# omicron2.net
KiCad netlist of a schematic drawn in EAGLE
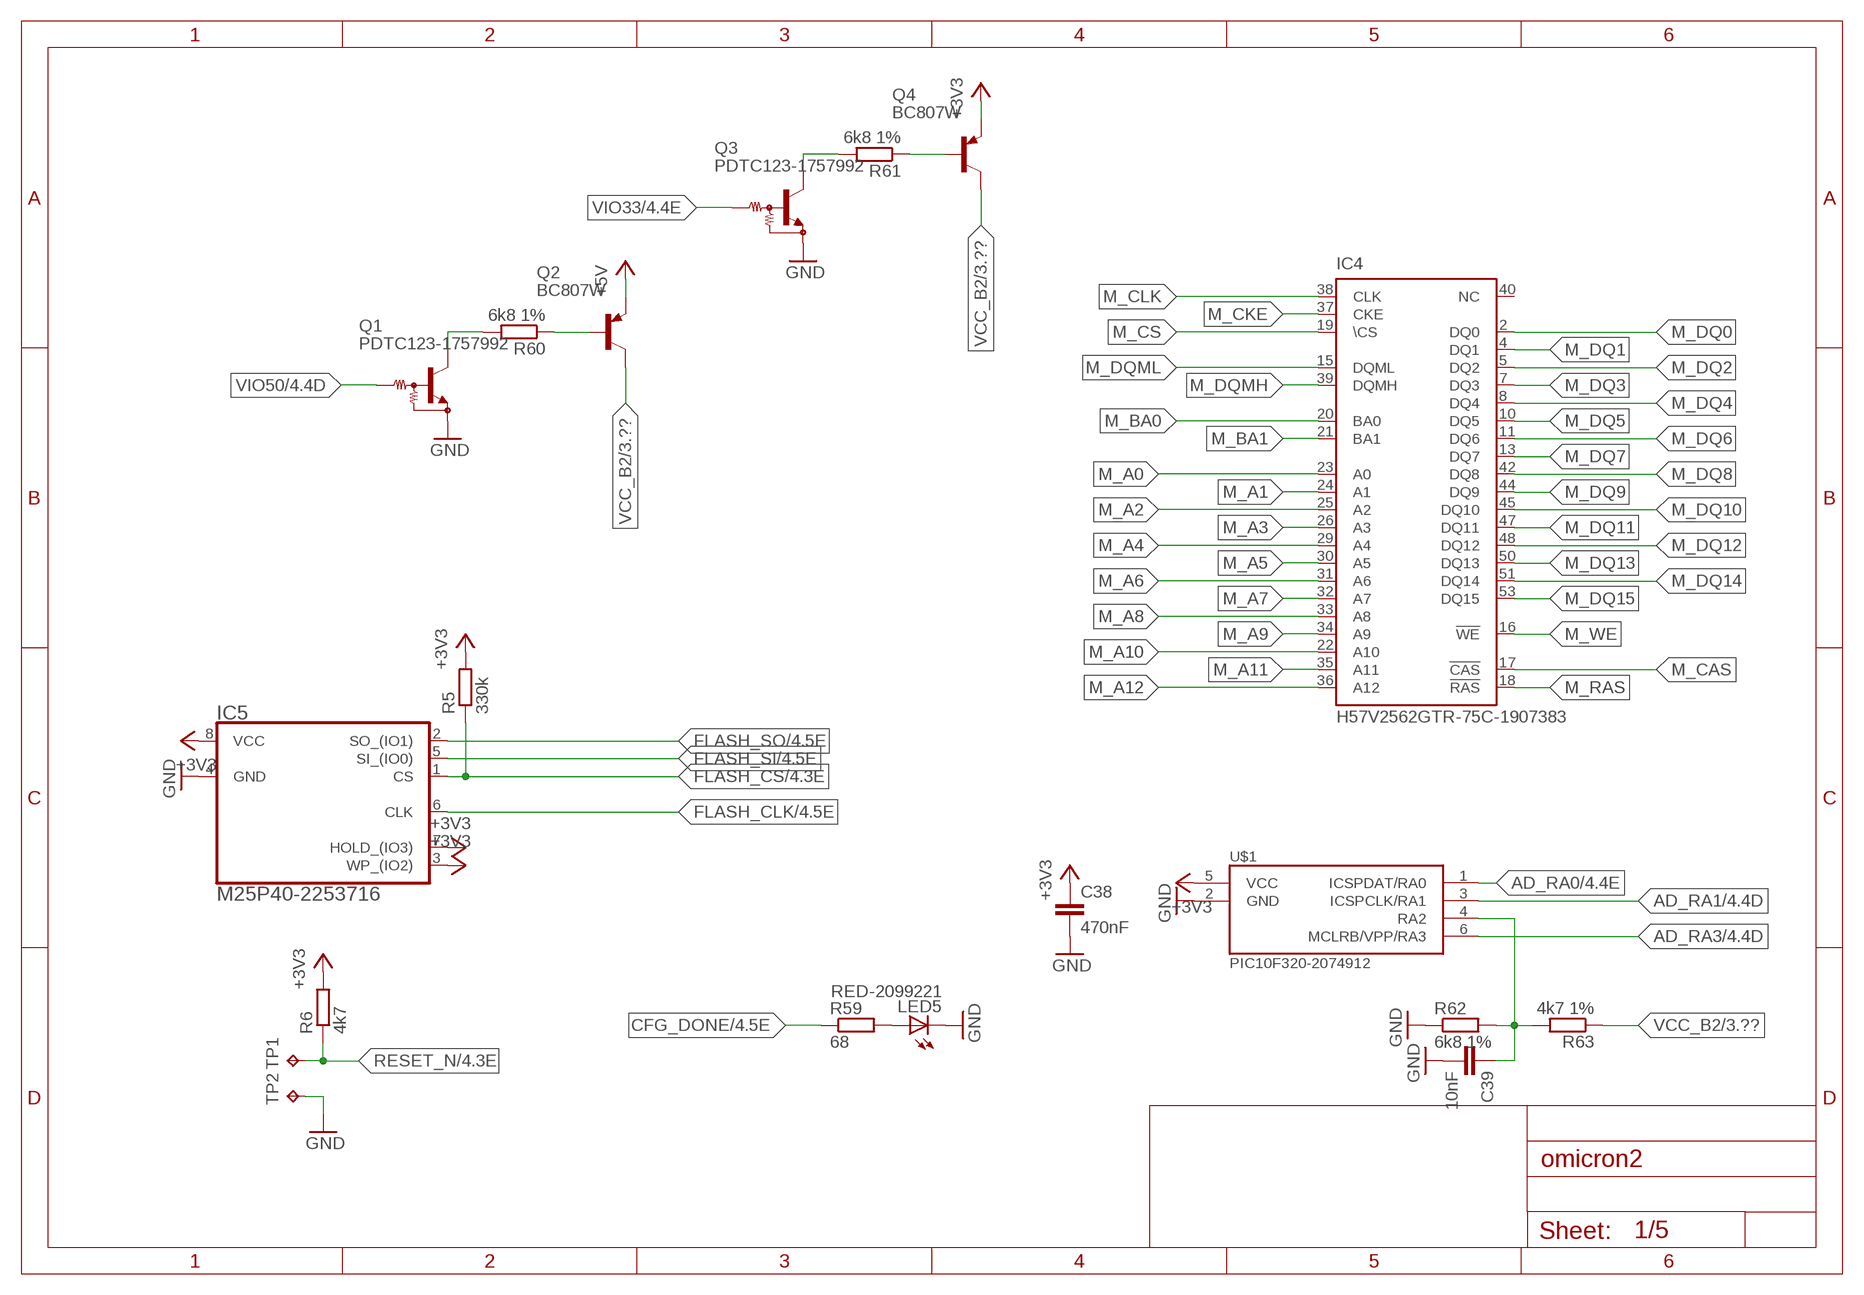
[diagram p0: schematic, sheet 1]
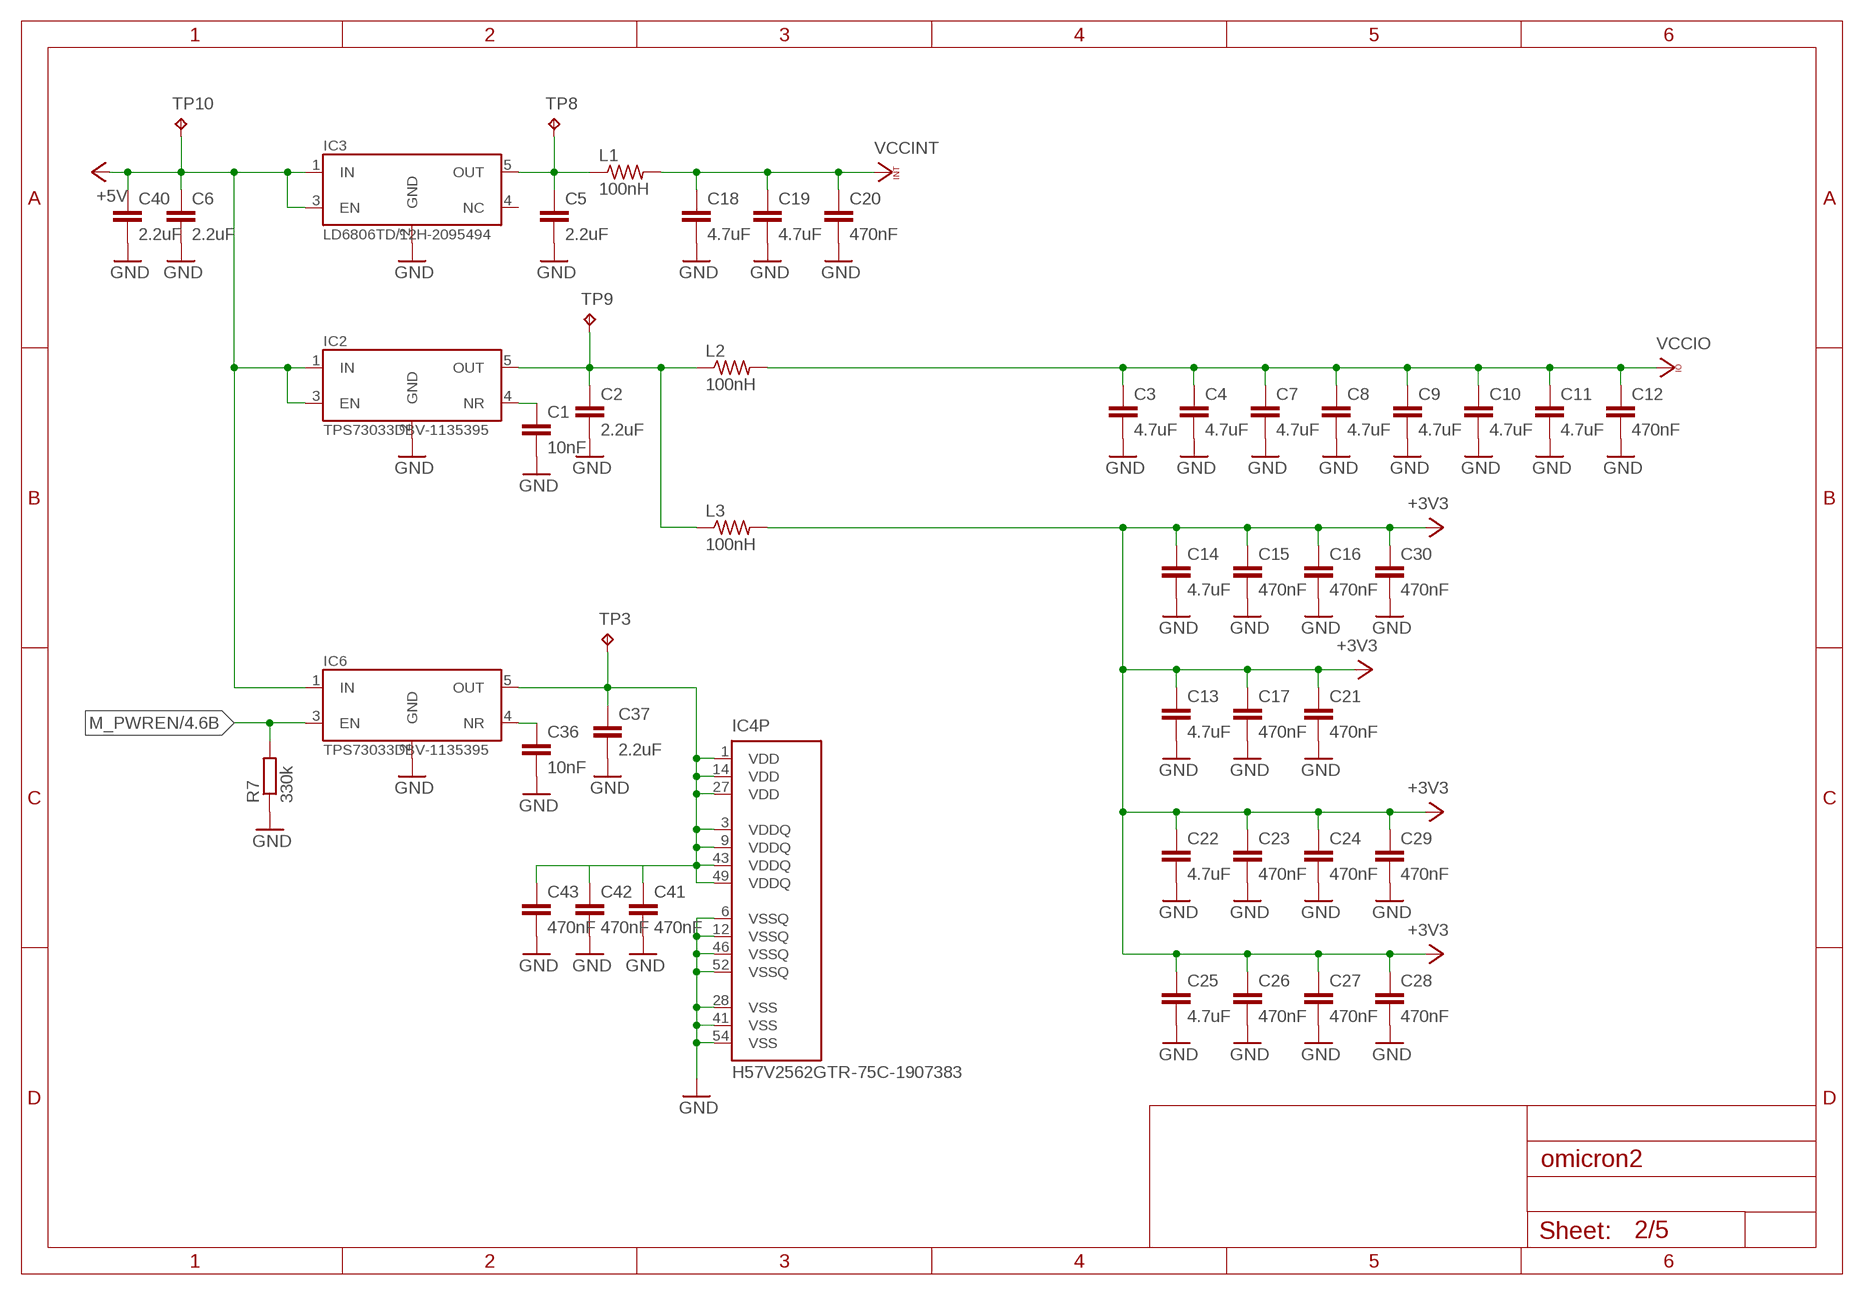
[diagram p1: schematic, sheet 2]
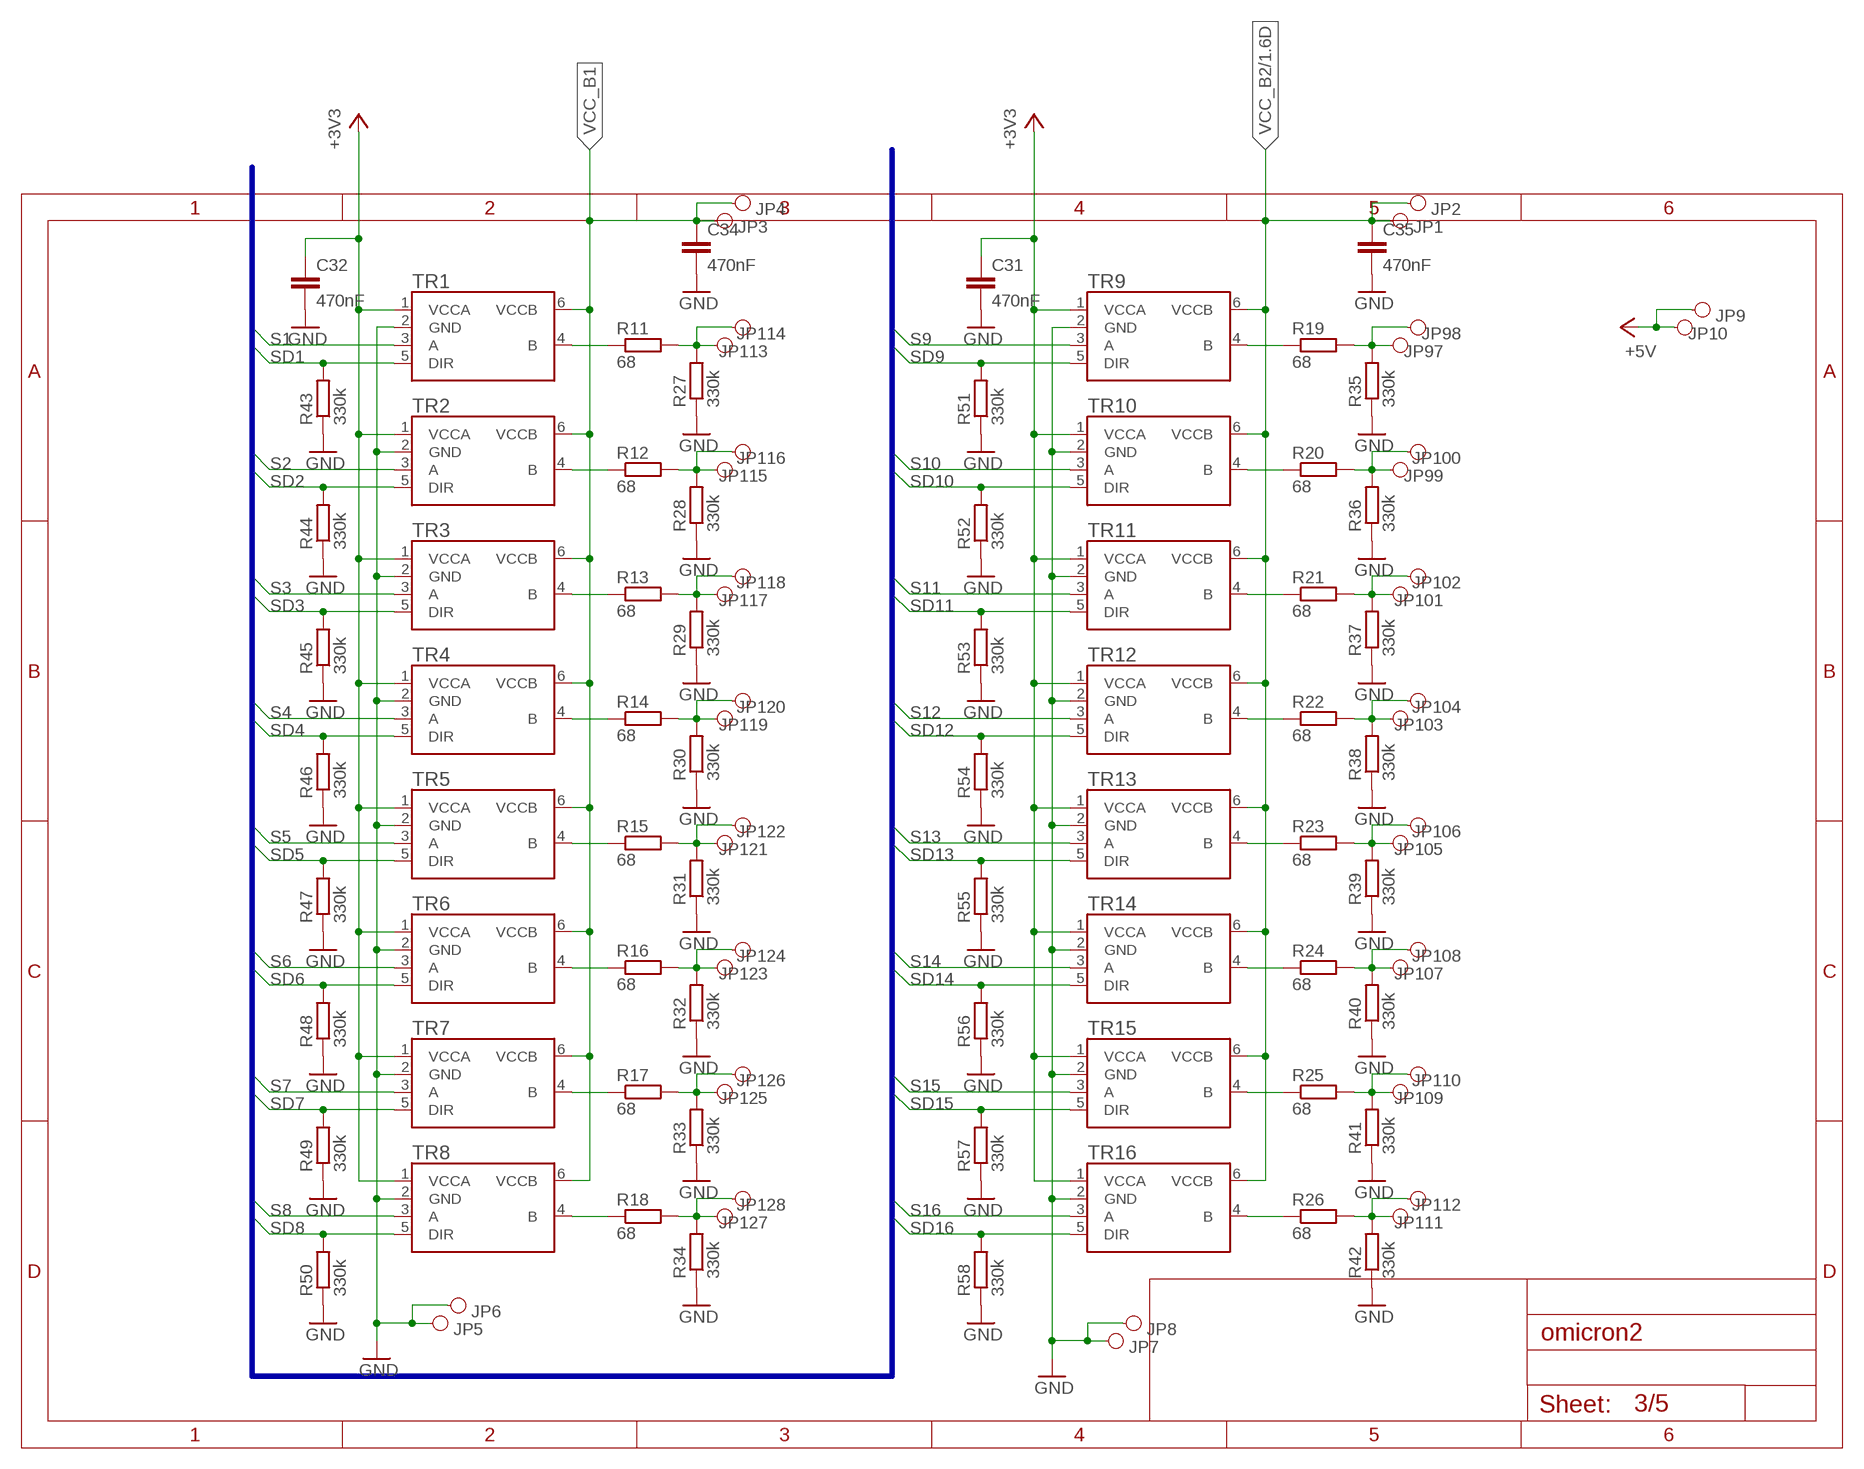
[diagram p2: schematic, sheet 3]
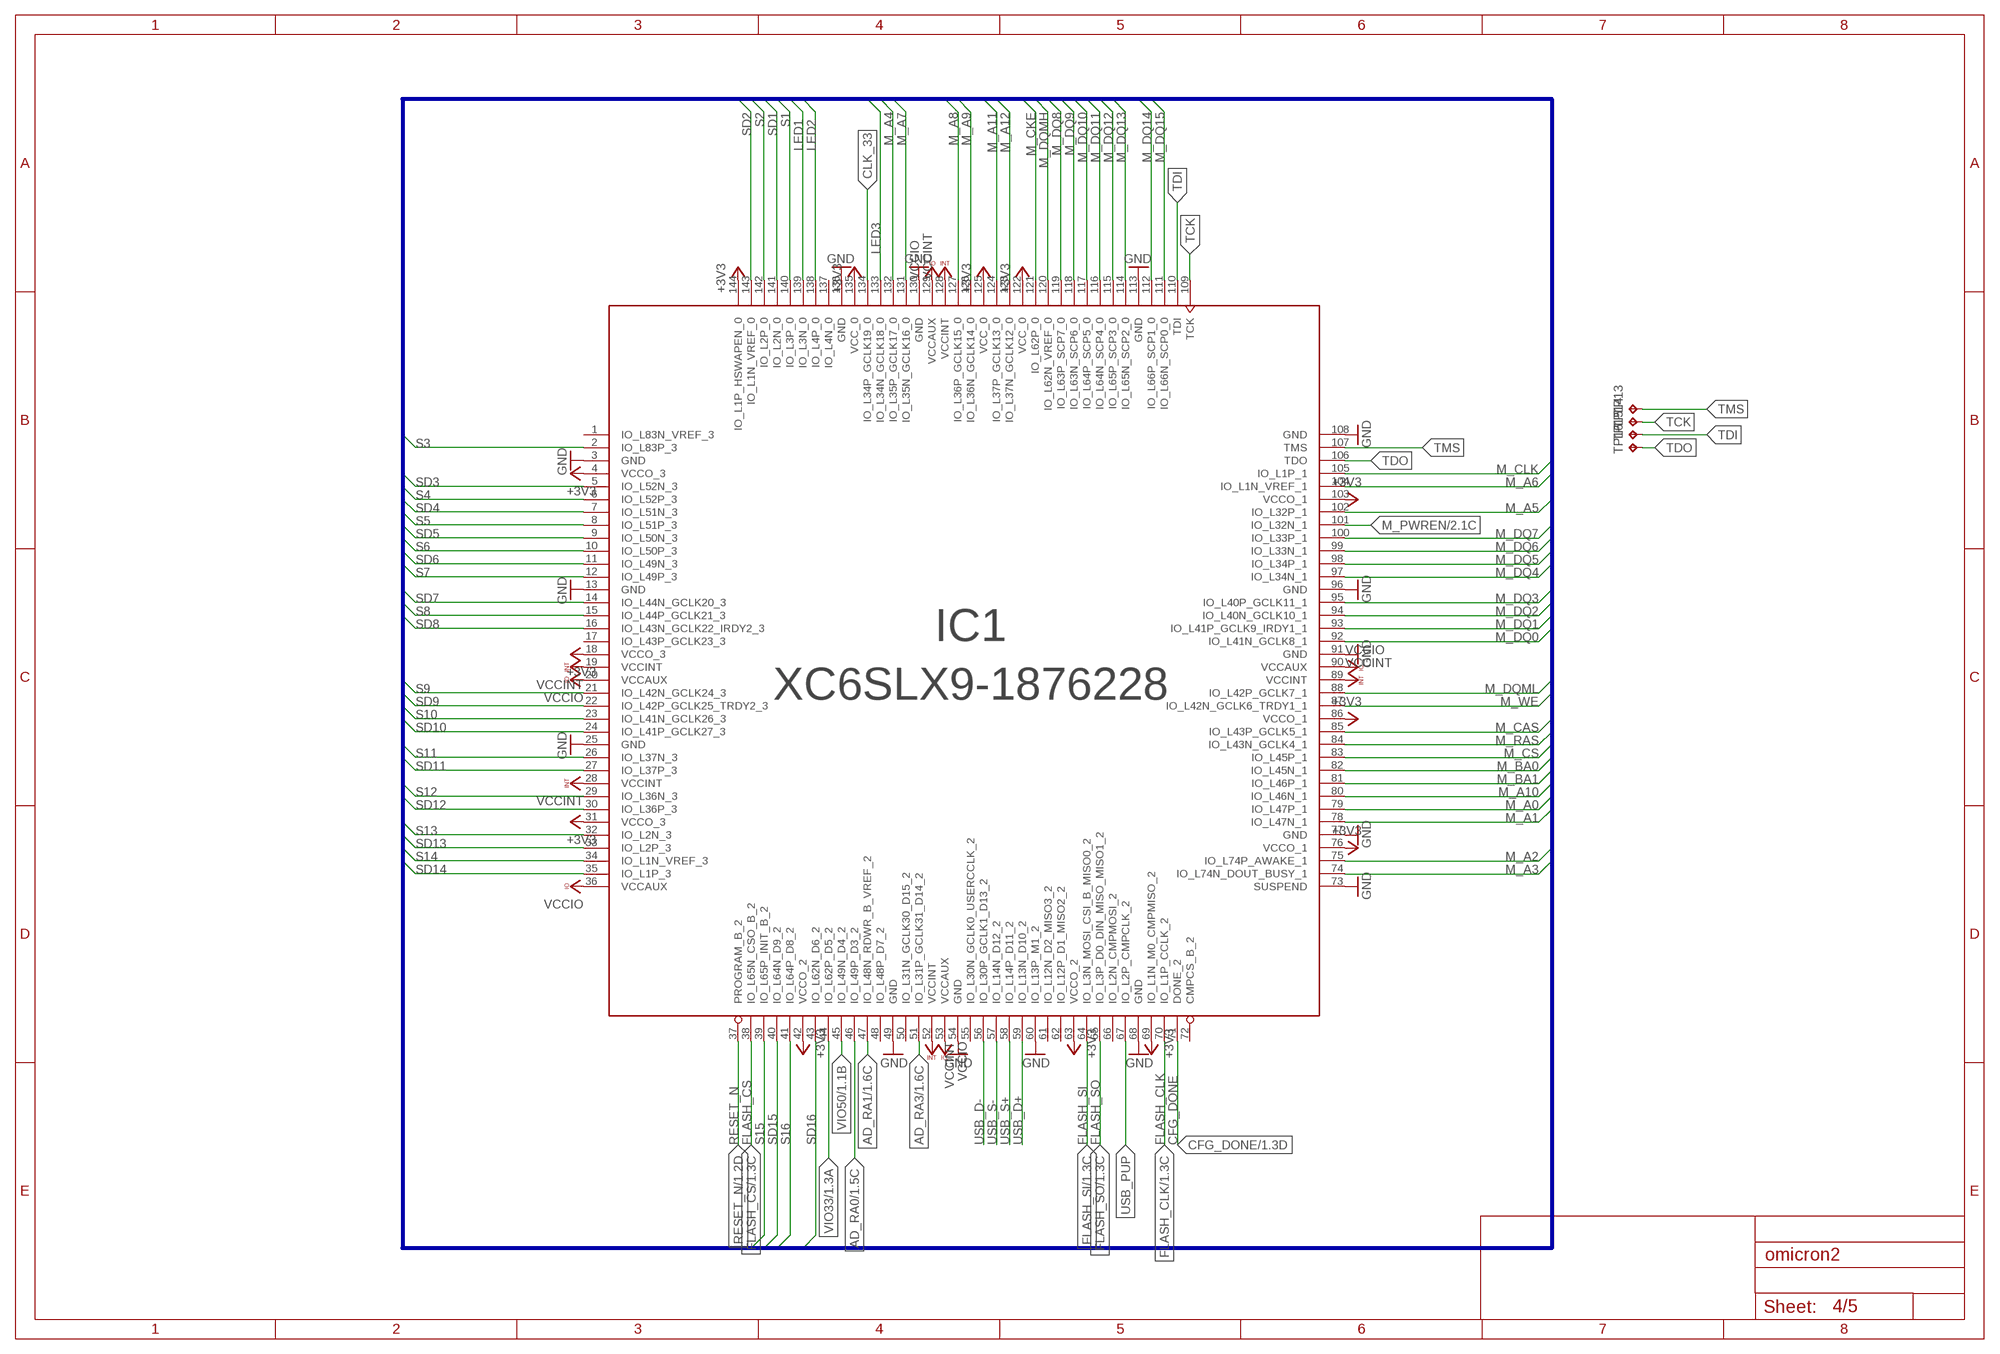
[diagram p3: schematic, sheet 4]
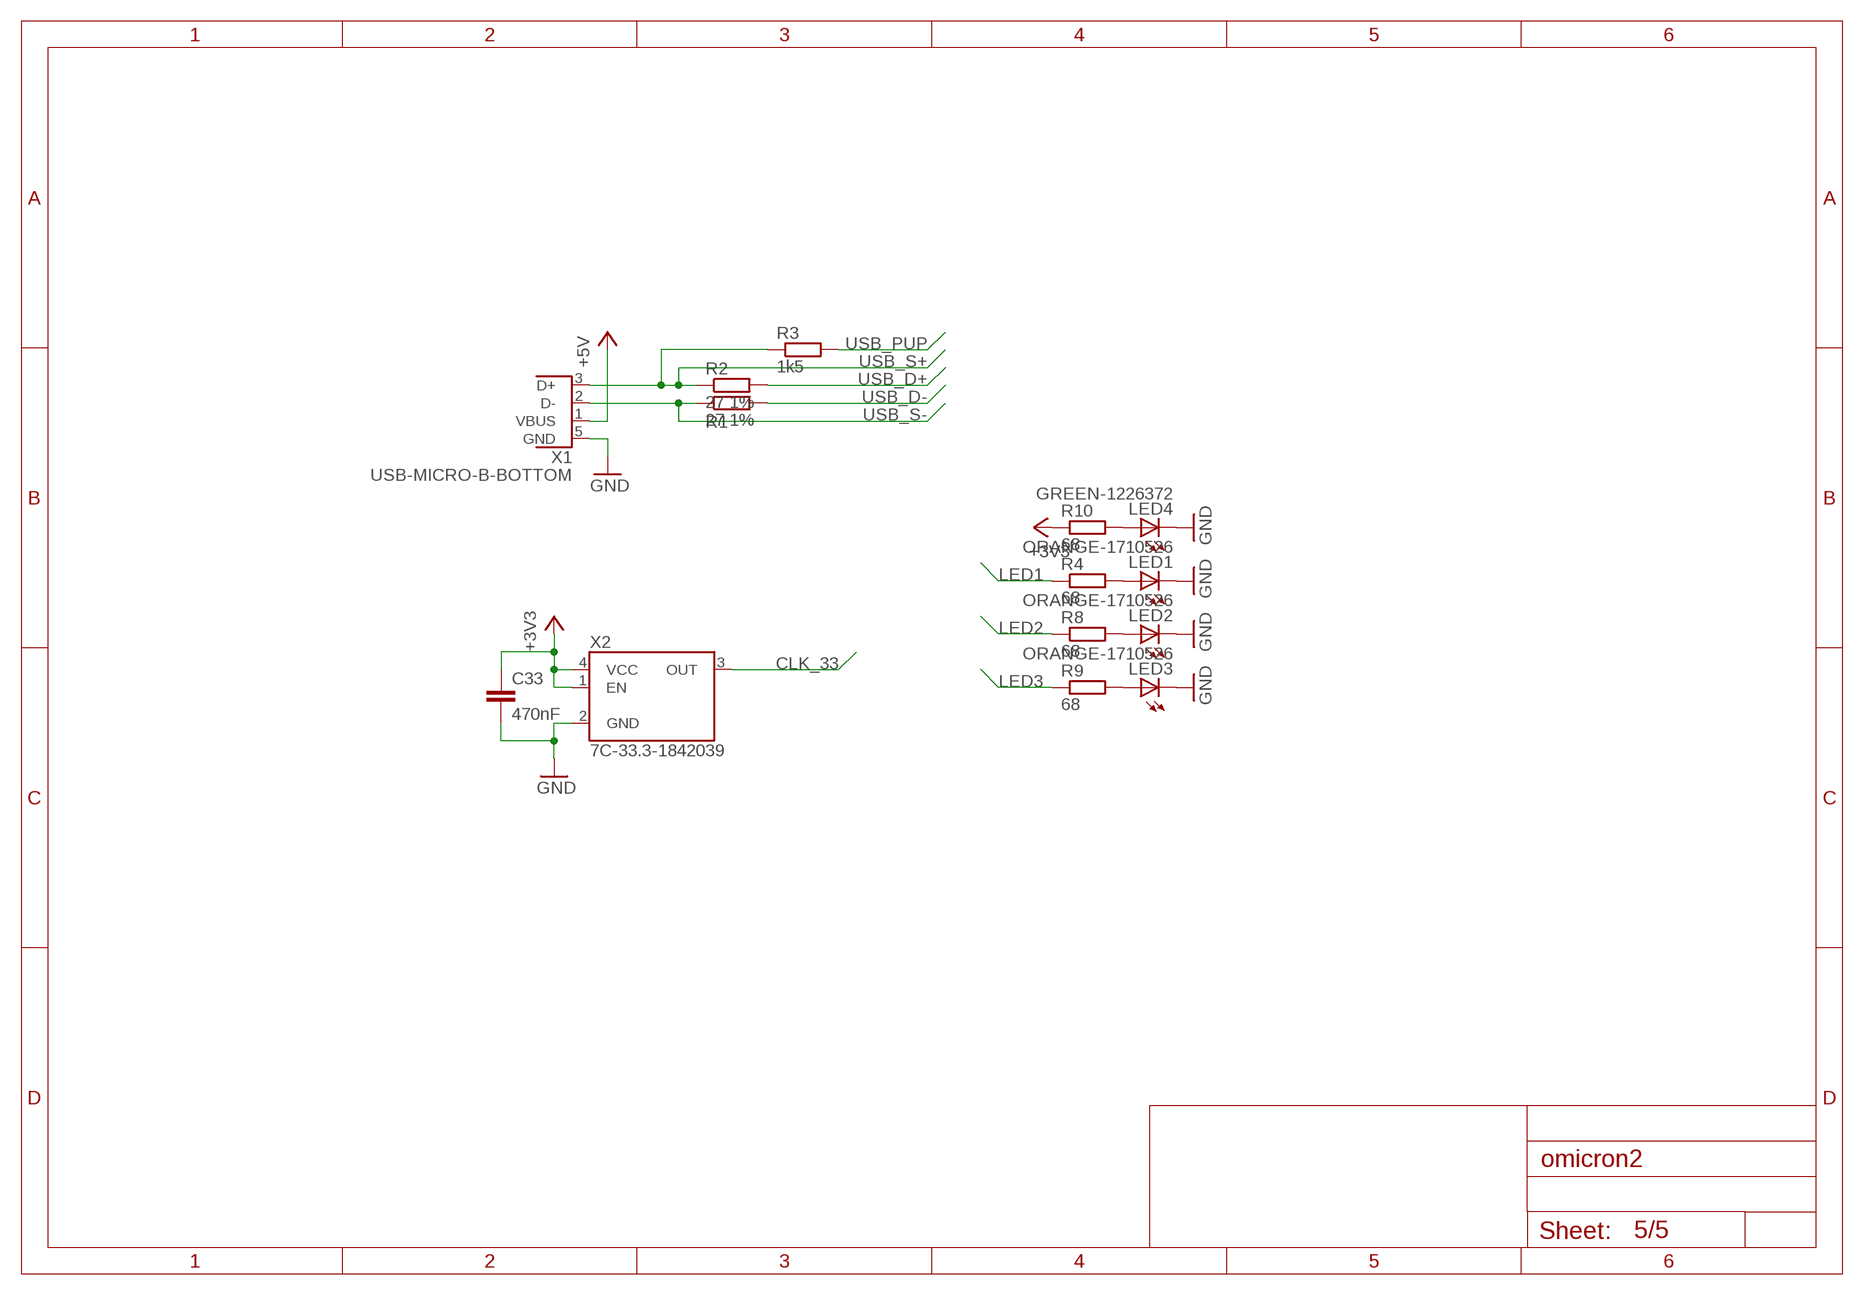
[diagram p4: schematic, sheet 5]

(export (version "E")
  (design (tool "Eeschema 10.0.6"))
  (components
    (comp (ref "C31")
      (value "470nF")
      (footprint "eagle-import:C0603")
      (libsource (lib "eagle-import") (part "C-EUC0603"))
    )
    (comp (ref "C32")
      (value "470nF")
      (footprint "eagle-import:C0603")
      (libsource (lib "eagle-import") (part "C-EUC0603"))
    )
    (comp (ref "C34")
      (value "470nF")
      (footprint "eagle-import:C0603")
      (libsource (lib "eagle-import") (part "C-EUC0603"))
    )
    (comp (ref "C35")
      (value "470nF")
      (footprint "eagle-import:C0603")
      (libsource (lib "eagle-import") (part "C-EUC0603"))
    )
    (comp (ref "JP1")
      (value "PINH1X01SMD")
      (footprint "eagle-import:PINH1X01SMD")
      (libsource (lib "eagle-import") (part "PINH1X01SMD"))
    )
    (comp (ref "JP2")
      (value "PINH1X01SMD")
      (footprint "eagle-import:PINH1X01SMD")
      (libsource (lib "eagle-import") (part "PINH1X01SMD"))
    )
    (comp (ref "JP3")
      (value "PINH1X01SMD")
      (footprint "eagle-import:PINH1X01SMD")
      (libsource (lib "eagle-import") (part "PINH1X01SMD"))
    )
    (comp (ref "JP4")
      (value "PINH1X01SMD")
      (footprint "eagle-import:PINH1X01SMD")
      (libsource (lib "eagle-import") (part "PINH1X01SMD"))
    )
    (comp (ref "JP5")
      (value "PINH1X01SMD")
      (footprint "eagle-import:PINH1X01SMD")
      (libsource (lib "eagle-import") (part "PINH1X01SMD"))
    )
    (comp (ref "JP6")
      (value "PINH1X01SMD")
      (footprint "eagle-import:PINH1X01SMD")
      (libsource (lib "eagle-import") (part "PINH1X01SMD"))
    )
    (comp (ref "JP7")
      (value "PINH1X01SMD")
      (footprint "eagle-import:PINH1X01SMD")
      (libsource (lib "eagle-import") (part "PINH1X01SMD"))
    )
    (comp (ref "JP8")
      (value "PINH1X01SMD")
      (footprint "eagle-import:PINH1X01SMD")
      (libsource (lib "eagle-import") (part "PINH1X01SMD"))
    )
    (comp (ref "JP9")
      (value "PINH1X01SMD")
      (footprint "eagle-import:PINH1X01SMD")
      (libsource (lib "eagle-import") (part "PINH1X01SMD"))
    )
    (comp (ref "JP10")
      (value "PINH1X01SMD")
      (footprint "eagle-import:PINH1X01SMD")
      (libsource (lib "eagle-import") (part "PINH1X01SMD"))
    )
    (comp (ref "JP97")
      (value "PINH1X01SMD")
      (footprint "eagle-import:PINH1X01SMD")
      (libsource (lib "eagle-import") (part "PINH1X01SMD"))
    )
    (comp (ref "JP98")
      (value "PINH1X01SMD")
      (footprint "eagle-import:PINH1X01SMD")
      (libsource (lib "eagle-import") (part "PINH1X01SMD"))
    )
    (comp (ref "JP99")
      (value "PINH1X01SMD")
      (footprint "eagle-import:PINH1X01SMD")
      (libsource (lib "eagle-import") (part "PINH1X01SMD"))
    )
    (comp (ref "JP100")
      (value "PINH1X01SMD")
      (footprint "eagle-import:PINH1X01SMD")
      (libsource (lib "eagle-import") (part "PINH1X01SMD"))
    )
    (comp (ref "JP101")
      (value "PINH1X01SMD")
      (footprint "eagle-import:PINH1X01SMD")
      (libsource (lib "eagle-import") (part "PINH1X01SMD"))
    )
    (comp (ref "JP102")
      (value "PINH1X01SMD")
      (footprint "eagle-import:PINH1X01SMD")
      (libsource (lib "eagle-import") (part "PINH1X01SMD"))
    )
    (comp (ref "JP103")
      (value "PINH1X01SMD")
      (footprint "eagle-import:PINH1X01SMD")
      (libsource (lib "eagle-import") (part "PINH1X01SMD"))
    )
    (comp (ref "JP104")
      (value "PINH1X01SMD")
      (footprint "eagle-import:PINH1X01SMD")
      (libsource (lib "eagle-import") (part "PINH1X01SMD"))
    )
    (comp (ref "JP105")
      (value "PINH1X01SMD")
      (footprint "eagle-import:PINH1X01SMD")
      (libsource (lib "eagle-import") (part "PINH1X01SMD"))
    )
    (comp (ref "JP106")
      (value "PINH1X01SMD")
      (footprint "eagle-import:PINH1X01SMD")
      (libsource (lib "eagle-import") (part "PINH1X01SMD"))
    )
    (comp (ref "JP107")
      (value "PINH1X01SMD")
      (footprint "eagle-import:PINH1X01SMD")
      (libsource (lib "eagle-import") (part "PINH1X01SMD"))
    )
    (comp (ref "JP108")
      (value "PINH1X01SMD")
      (footprint "eagle-import:PINH1X01SMD")
      (libsource (lib "eagle-import") (part "PINH1X01SMD"))
    )
    (comp (ref "JP109")
      (value "PINH1X01SMD")
      (footprint "eagle-import:PINH1X01SMD")
      (libsource (lib "eagle-import") (part "PINH1X01SMD"))
    )
    (comp (ref "JP110")
      (value "PINH1X01SMD")
      (footprint "eagle-import:PINH1X01SMD")
      (libsource (lib "eagle-import") (part "PINH1X01SMD"))
    )
    (comp (ref "JP111")
      (value "PINH1X01SMD")
      (footprint "eagle-import:PINH1X01SMD")
      (libsource (lib "eagle-import") (part "PINH1X01SMD"))
    )
    (comp (ref "JP112")
      (value "PINH1X01SMD")
      (footprint "eagle-import:PINH1X01SMD")
      (libsource (lib "eagle-import") (part "PINH1X01SMD"))
    )
    (comp (ref "JP113")
      (value "PINH1X01SMD")
      (footprint "eagle-import:PINH1X01SMD")
      (libsource (lib "eagle-import") (part "PINH1X01SMD"))
    )
    (comp (ref "JP114")
      (value "PINH1X01SMD")
      (footprint "eagle-import:PINH1X01SMD")
      (libsource (lib "eagle-import") (part "PINH1X01SMD"))
    )
    (comp (ref "JP115")
      (value "PINH1X01SMD")
      (footprint "eagle-import:PINH1X01SMD")
      (libsource (lib "eagle-import") (part "PINH1X01SMD"))
    )
    (comp (ref "JP116")
      (value "PINH1X01SMD")
      (footprint "eagle-import:PINH1X01SMD")
      (libsource (lib "eagle-import") (part "PINH1X01SMD"))
    )
    (comp (ref "JP117")
      (value "PINH1X01SMD")
      (footprint "eagle-import:PINH1X01SMD")
      (libsource (lib "eagle-import") (part "PINH1X01SMD"))
    )
    (comp (ref "JP118")
      (value "PINH1X01SMD")
      (footprint "eagle-import:PINH1X01SMD")
      (libsource (lib "eagle-import") (part "PINH1X01SMD"))
    )
    (comp (ref "JP119")
      (value "PINH1X01SMD")
      (footprint "eagle-import:PINH1X01SMD")
      (libsource (lib "eagle-import") (part "PINH1X01SMD"))
    )
    (comp (ref "JP120")
      (value "PINH1X01SMD")
      (footprint "eagle-import:PINH1X01SMD")
      (libsource (lib "eagle-import") (part "PINH1X01SMD"))
    )
    (comp (ref "JP121")
      (value "PINH1X01SMD")
      (footprint "eagle-import:PINH1X01SMD")
      (libsource (lib "eagle-import") (part "PINH1X01SMD"))
    )
    (comp (ref "JP122")
      (value "PINH1X01SMD")
      (footprint "eagle-import:PINH1X01SMD")
      (libsource (lib "eagle-import") (part "PINH1X01SMD"))
    )
    (comp (ref "JP123")
      (value "PINH1X01SMD")
      (footprint "eagle-import:PINH1X01SMD")
      (libsource (lib "eagle-import") (part "PINH1X01SMD"))
    )
    (comp (ref "JP124")
      (value "PINH1X01SMD")
      (footprint "eagle-import:PINH1X01SMD")
      (libsource (lib "eagle-import") (part "PINH1X01SMD"))
    )
    (comp (ref "JP125")
      (value "PINH1X01SMD")
      (footprint "eagle-import:PINH1X01SMD")
      (libsource (lib "eagle-import") (part "PINH1X01SMD"))
    )
    (comp (ref "JP126")
      (value "PINH1X01SMD")
      (footprint "eagle-import:PINH1X01SMD")
      (libsource (lib "eagle-import") (part "PINH1X01SMD"))
    )
    (comp (ref "JP127")
      (value "PINH1X01SMD")
      (footprint "eagle-import:PINH1X01SMD")
      (libsource (lib "eagle-import") (part "PINH1X01SMD"))
    )
    (comp (ref "JP128")
      (value "PINH1X01SMD")
      (footprint "eagle-import:PINH1X01SMD")
      (libsource (lib "eagle-import") (part "PINH1X01SMD"))
    )
    (comp (ref "R11")
      (value "68")
      (footprint "eagle-import:R0603")
      (libsource (lib "eagle-import") (part "R-EU_R0603"))
    )
    (comp (ref "R12")
      (value "68")
      (footprint "eagle-import:R0603")
      (libsource (lib "eagle-import") (part "R-EU_R0603"))
    )
    (comp (ref "R13")
      (value "68")
      (footprint "eagle-import:R0603")
      (libsource (lib "eagle-import") (part "R-EU_R0603"))
    )
    (comp (ref "R14")
      (value "68")
      (footprint "eagle-import:R0603")
      (libsource (lib "eagle-import") (part "R-EU_R0603"))
    )
    (comp (ref "R15")
      (value "68")
      (footprint "eagle-import:R0603")
      (libsource (lib "eagle-import") (part "R-EU_R0603"))
    )
    (comp (ref "R16")
      (value "68")
      (footprint "eagle-import:R0603")
      (libsource (lib "eagle-import") (part "R-EU_R0603"))
    )
    (comp (ref "R17")
      (value "68")
      (footprint "eagle-import:R0603")
      (libsource (lib "eagle-import") (part "R-EU_R0603"))
    )
    (comp (ref "R18")
      (value "68")
      (footprint "eagle-import:R0603")
      (libsource (lib "eagle-import") (part "R-EU_R0603"))
    )
    (comp (ref "R19")
      (value "68")
      (footprint "eagle-import:R0603")
      (libsource (lib "eagle-import") (part "R-EU_R0603"))
    )
    (comp (ref "R20")
      (value "68")
      (footprint "eagle-import:R0603")
      (libsource (lib "eagle-import") (part "R-EU_R0603"))
    )
    (comp (ref "R21")
      (value "68")
      (footprint "eagle-import:R0603")
      (libsource (lib "eagle-import") (part "R-EU_R0603"))
    )
    (comp (ref "R22")
      (value "68")
      (footprint "eagle-import:R0603")
      (libsource (lib "eagle-import") (part "R-EU_R0603"))
    )
    (comp (ref "R23")
      (value "68")
      (footprint "eagle-import:R0603")
      (libsource (lib "eagle-import") (part "R-EU_R0603"))
    )
    (comp (ref "R24")
      (value "68")
      (footprint "eagle-import:R0603")
      (libsource (lib "eagle-import") (part "R-EU_R0603"))
    )
    (comp (ref "R25")
      (value "68")
      (footprint "eagle-import:R0603")
      (libsource (lib "eagle-import") (part "R-EU_R0603"))
    )
    (comp (ref "R26")
      (value "68")
      (footprint "eagle-import:R0603")
      (libsource (lib "eagle-import") (part "R-EU_R0603"))
    )
    (comp (ref "R27")
      (value "330k")
      (footprint "eagle-import:R0603")
      (libsource (lib "eagle-import") (part "R-EU_R0603"))
    )
    (comp (ref "R28")
      (value "330k")
      (footprint "eagle-import:R0603")
      (libsource (lib "eagle-import") (part "R-EU_R0603"))
    )
    (comp (ref "R29")
      (value "330k")
      (footprint "eagle-import:R0603")
      (libsource (lib "eagle-import") (part "R-EU_R0603"))
    )
    (comp (ref "R30")
      (value "330k")
      (footprint "eagle-import:R0603")
      (libsource (lib "eagle-import") (part "R-EU_R0603"))
    )
    (comp (ref "R31")
      (value "330k")
      (footprint "eagle-import:R0603")
      (libsource (lib "eagle-import") (part "R-EU_R0603"))
    )
    (comp (ref "R32")
      (value "330k")
      (footprint "eagle-import:R0603")
      (libsource (lib "eagle-import") (part "R-EU_R0603"))
    )
    (comp (ref "R33")
      (value "330k")
      (footprint "eagle-import:R0603")
      (libsource (lib "eagle-import") (part "R-EU_R0603"))
    )
    (comp (ref "R34")
      (value "330k")
      (footprint "eagle-import:R0603")
      (libsource (lib "eagle-import") (part "R-EU_R0603"))
    )
    (comp (ref "R35")
      (value "330k")
      (footprint "eagle-import:R0603")
      (libsource (lib "eagle-import") (part "R-EU_R0603"))
    )
    (comp (ref "R36")
      (value "330k")
      (footprint "eagle-import:R0603")
      (libsource (lib "eagle-import") (part "R-EU_R0603"))
    )
    (comp (ref "R37")
      (value "330k")
      (footprint "eagle-import:R0603")
      (libsource (lib "eagle-import") (part "R-EU_R0603"))
    )
    (comp (ref "R38")
      (value "330k")
      (footprint "eagle-import:R0603")
      (libsource (lib "eagle-import") (part "R-EU_R0603"))
    )
    (comp (ref "R39")
      (value "330k")
      (footprint "eagle-import:R0603")
      (libsource (lib "eagle-import") (part "R-EU_R0603"))
    )
    (comp (ref "R40")
      (value "330k")
      (footprint "eagle-import:R0603")
      (libsource (lib "eagle-import") (part "R-EU_R0603"))
    )
    (comp (ref "R41")
      (value "330k")
      (footprint "eagle-import:R0603")
      (libsource (lib "eagle-import") (part "R-EU_R0603"))
    )
    (comp (ref "R42")
      (value "330k")
      (footprint "eagle-import:R0603")
      (libsource (lib "eagle-import") (part "R-EU_R0603"))
    )
    (comp (ref "R43")
      (value "330k")
      (footprint "eagle-import:R0603")
      (libsource (lib "eagle-import") (part "R-EU_R0603"))
    )
    (comp (ref "R44")
      (value "330k")
      (footprint "eagle-import:R0603")
      (libsource (lib "eagle-import") (part "R-EU_R0603"))
    )
    (comp (ref "R45")
      (value "330k")
      (footprint "eagle-import:R0603")
      (libsource (lib "eagle-import") (part "R-EU_R0603"))
    )
    (comp (ref "R46")
      (value "330k")
      (footprint "eagle-import:R0603")
      (libsource (lib "eagle-import") (part "R-EU_R0603"))
    )
    (comp (ref "R47")
      (value "330k")
      (footprint "eagle-import:R0603")
      (libsource (lib "eagle-import") (part "R-EU_R0603"))
    )
    (comp (ref "R48")
      (value "330k")
      (footprint "eagle-import:R0603")
      (libsource (lib "eagle-import") (part "R-EU_R0603"))
    )
    (comp (ref "R49")
      (value "330k")
      (footprint "eagle-import:R0603")
      (libsource (lib "eagle-import") (part "R-EU_R0603"))
    )
    (comp (ref "R50")
      (value "330k")
      (footprint "eagle-import:R0603")
      (libsource (lib "eagle-import") (part "R-EU_R0603"))
    )
    (comp (ref "R51")
      (value "330k")
      (footprint "eagle-import:R0603")
      (libsource (lib "eagle-import") (part "R-EU_R0603"))
    )
    (comp (ref "R52")
      (value "330k")
      (footprint "eagle-import:R0603")
      (libsource (lib "eagle-import") (part "R-EU_R0603"))
    )
    (comp (ref "R53")
      (value "330k")
      (footprint "eagle-import:R0603")
      (libsource (lib "eagle-import") (part "R-EU_R0603"))
    )
    (comp (ref "R54")
      (value "330k")
      (footprint "eagle-import:R0603")
      (libsource (lib "eagle-import") (part "R-EU_R0603"))
    )
    (comp (ref "R55")
      (value "330k")
      (footprint "eagle-import:R0603")
      (libsource (lib "eagle-import") (part "R-EU_R0603"))
    )
    (comp (ref "R56")
      (value "330k")
      (footprint "eagle-import:R0603")
      (libsource (lib "eagle-import") (part "R-EU_R0603"))
    )
    (comp (ref "R57")
      (value "330k")
      (footprint "eagle-import:R0603")
      (libsource (lib "eagle-import") (part "R-EU_R0603"))
    )
    (comp (ref "R58")
      (value "330k")
      (footprint "eagle-import:R0603")
      (libsource (lib "eagle-import") (part "R-EU_R0603"))
    )
    (comp (ref "TR1")
      (value "74LVC1T45DBV")
      (footprint "eagle-import:SOT236")
      (libsource (lib "eagle-import") (part "741T45DBVLVC"))
    )
    (comp (ref "TR2")
      (value "74LVC1T45DBV")
      (footprint "eagle-import:SOT236")
      (libsource (lib "eagle-import") (part "741T45DBVLVC"))
    )
    (comp (ref "TR3")
      (value "74LVC1T45DBV")
      (footprint "eagle-import:SOT236")
      (libsource (lib "eagle-import") (part "741T45DBVLVC"))
    )
    (comp (ref "TR4")
      (value "74LVC1T45DBV")
      (footprint "eagle-import:SOT236")
      (libsource (lib "eagle-import") (part "741T45DBVLVC"))
    )
    (comp (ref "TR5")
      (value "74LVC1T45DBV")
      (footprint "eagle-import:SOT236")
      (libsource (lib "eagle-import") (part "741T45DBVLVC"))
    )
    (comp (ref "TR6")
      (value "74LVC1T45DBV")
      (footprint "eagle-import:SOT236")
      (libsource (lib "eagle-import") (part "741T45DBVLVC"))
    )
    (comp (ref "TR7")
      (value "74LVC1T45DBV")
      (footprint "eagle-import:SOT236")
      (libsource (lib "eagle-import") (part "741T45DBVLVC"))
    )
    (comp (ref "TR8")
      (value "74LVC1T45DBV")
      (footprint "eagle-import:SOT236")
      (libsource (lib "eagle-import") (part "741T45DBVLVC"))
    )
    (comp (ref "TR9")
      (value "74LVC1T45DBV")
      (footprint "eagle-import:SOT236")
      (libsource (lib "eagle-import") (part "741T45DBVLVC"))
    )
    (comp (ref "TR10")
      (value "74LVC1T45DBV")
      (footprint "eagle-import:SOT236")
      (libsource (lib "eagle-import") (part "741T45DBVLVC"))
    )
    (comp (ref "TR11")
      (value "74LVC1T45DBV")
      (footprint "eagle-import:SOT236")
      (libsource (lib "eagle-import") (part "741T45DBVLVC"))
    )
    (comp (ref "TR12")
      (value "74LVC1T45DBV")
      (footprint "eagle-import:SOT236")
      (libsource (lib "eagle-import") (part "741T45DBVLVC"))
    )
    (comp (ref "TR13")
      (value "74LVC1T45DBV")
      (footprint "eagle-import:SOT236")
      (libsource (lib "eagle-import") (part "741T45DBVLVC"))
    )
    (comp (ref "TR14")
      (value "74LVC1T45DBV")
      (footprint "eagle-import:SOT236")
      (libsource (lib "eagle-import") (part "741T45DBVLVC"))
    )
    (comp (ref "TR15")
      (value "74LVC1T45DBV")
      (footprint "eagle-import:SOT236")
      (libsource (lib "eagle-import") (part "741T45DBVLVC"))
    )
    (comp (ref "TR16")
      (value "74LVC1T45DBV")
      (footprint "eagle-import:SOT236")
      (libsource (lib "eagle-import") (part "741T45DBVLVC"))
    )
    (comp (ref "C33")
      (value "470nF")
      (footprint "eagle-import:C0603")
      (libsource (lib "eagle-import") (part "C-EUC0603"))
    )
    (comp (ref "LED1")
      (value "ORANGE-1710526")
      (footprint "eagle-import:CHIPLED_0603")
      (libsource (lib "eagle-import") (part "LEDCHIPLED_0603"))
    )
    (comp (ref "LED2")
      (value "ORANGE-1710526")
      (footprint "eagle-import:CHIPLED_0603")
      (libsource (lib "eagle-import") (part "LEDCHIPLED_0603"))
    )
    (comp (ref "LED3")
      (value "ORANGE-1710526")
      (footprint "eagle-import:CHIPLED_0603")
      (libsource (lib "eagle-import") (part "LEDCHIPLED_0603"))
    )
    (comp (ref "LED4")
      (value "GREEN-1226372")
      (footprint "eagle-import:CHIPLED_0603")
      (libsource (lib "eagle-import") (part "LEDCHIPLED_0603"))
    )
    (comp (ref "R1")
      (value "27 1%")
      (footprint "eagle-import:R0603")
      (libsource (lib "eagle-import") (part "R-EU_R0603"))
    )
    (comp (ref "R2")
      (value "27 1%")
      (footprint "eagle-import:R0603")
      (libsource (lib "eagle-import") (part "R-EU_R0603"))
    )
    (comp (ref "R3")
      (value "1k5")
      (footprint "eagle-import:R0603")
      (libsource (lib "eagle-import") (part "R-EU_R0603"))
    )
    (comp (ref "R4")
      (value "68")
      (footprint "eagle-import:R0603")
      (libsource (lib "eagle-import") (part "R-EU_R0603"))
    )
    (comp (ref "R8")
      (value "68")
      (footprint "eagle-import:R0603")
      (libsource (lib "eagle-import") (part "R-EU_R0603"))
    )
    (comp (ref "R9")
      (value "68")
      (footprint "eagle-import:R0603")
      (libsource (lib "eagle-import") (part "R-EU_R0603"))
    )
    (comp (ref "R10")
      (value "68")
      (footprint "eagle-import:R0603")
      (libsource (lib "eagle-import") (part "R-EU_R0603"))
    )
    (comp (ref "X1")
      (value "USB-MICRO-B-BOTTOM")
      (footprint "eagle-import:USB-MICRO-B-BOTTOM-MOLEX")
      (libsource (lib "eagle-import") (part "USB-MICRO-B-BOTTOM"))
    )
    (comp (ref "X2")
      (value "7C-33.3-1842039")
      (footprint "eagle-import:5X3.2_HAND")
      (libsource (lib "eagle-import") (part "OSC-5X3.2HS"))
    )
    (comp (ref "C1")
      (value "10nF")
      (footprint "eagle-import:C0603")
      (libsource (lib "eagle-import") (part "C-EUC0603"))
    )
    (comp (ref "C2")
      (value "2.2uF")
      (footprint "eagle-import:C0603")
      (libsource (lib "eagle-import") (part "C-EUC0603"))
    )
    (comp (ref "C3")
      (value "4.7uF")
      (footprint "eagle-import:C0603")
      (libsource (lib "eagle-import") (part "C-EUC0603"))
    )
    (comp (ref "C4")
      (value "4.7uF")
      (footprint "eagle-import:C0603")
      (libsource (lib "eagle-import") (part "C-EUC0603"))
    )
    (comp (ref "C5")
      (value "2.2uF")
      (footprint "eagle-import:C0603")
      (libsource (lib "eagle-import") (part "C-EUC0603"))
    )
    (comp (ref "C6")
      (value "2.2uF")
      (footprint "eagle-import:C0603")
      (libsource (lib "eagle-import") (part "C-EUC0603"))
    )
    (comp (ref "C7")
      (value "4.7uF")
      (footprint "eagle-import:C0603")
      (libsource (lib "eagle-import") (part "C-EUC0603"))
    )
    (comp (ref "C8")
      (value "4.7uF")
      (footprint "eagle-import:C0603")
      (libsource (lib "eagle-import") (part "C-EUC0603"))
    )
    (comp (ref "C9")
      (value "4.7uF")
      (footprint "eagle-import:C0603")
      (libsource (lib "eagle-import") (part "C-EUC0603"))
    )
    (comp (ref "C10")
      (value "4.7uF")
      (footprint "eagle-import:C0603")
      (libsource (lib "eagle-import") (part "C-EUC0603"))
    )
    (comp (ref "C11")
      (value "4.7uF")
      (footprint "eagle-import:C0603")
      (libsource (lib "eagle-import") (part "C-EUC0603"))
    )
    (comp (ref "C12")
      (value "470nF")
      (footprint "eagle-import:C0603")
      (libsource (lib "eagle-import") (part "C-EUC0603"))
    )
    (comp (ref "C13")
      (value "4.7uF")
      (footprint "eagle-import:C0603")
      (libsource (lib "eagle-import") (part "C-EUC0603"))
    )
    (comp (ref "C14")
      (value "4.7uF")
      (footprint "eagle-import:C0603")
      (libsource (lib "eagle-import") (part "C-EUC0603"))
    )
    (comp (ref "C15")
      (value "470nF")
      (footprint "eagle-import:C0603")
      (libsource (lib "eagle-import") (part "C-EUC0603"))
    )
    (comp (ref "C16")
      (value "470nF")
      (footprint "eagle-import:C0603")
      (libsource (lib "eagle-import") (part "C-EUC0603"))
    )
    (comp (ref "C17")
      (value "470nF")
      (footprint "eagle-import:C0603")
      (libsource (lib "eagle-import") (part "C-EUC0603"))
    )
    (comp (ref "C18")
      (value "4.7uF")
      (footprint "eagle-import:C0603")
      (libsource (lib "eagle-import") (part "C-EUC0603"))
    )
    (comp (ref "C19")
      (value "4.7uF")
      (footprint "eagle-import:C0603")
      (libsource (lib "eagle-import") (part "C-EUC0603"))
    )
    (comp (ref "C20")
      (value "470nF")
      (footprint "eagle-import:C0603")
      (libsource (lib "eagle-import") (part "C-EUC0603"))
    )
    (comp (ref "C21")
      (value "470nF")
      (footprint "eagle-import:C0603")
      (libsource (lib "eagle-import") (part "C-EUC0603"))
    )
    (comp (ref "C22")
      (value "4.7uF")
      (footprint "eagle-import:C0603")
      (libsource (lib "eagle-import") (part "C-EUC0603"))
    )
    (comp (ref "C23")
      (value "470nF")
      (footprint "eagle-import:C0603")
      (libsource (lib "eagle-import") (part "C-EUC0603"))
    )
    (comp (ref "C24")
      (value "470nF")
      (footprint "eagle-import:C0603")
      (libsource (lib "eagle-import") (part "C-EUC0603"))
    )
    (comp (ref "C25")
      (value "4.7uF")
      (footprint "eagle-import:C0603")
      (libsource (lib "eagle-import") (part "C-EUC0603"))
    )
    (comp (ref "C26")
      (value "470nF")
      (footprint "eagle-import:C0603")
      (libsource (lib "eagle-import") (part "C-EUC0603"))
    )
    (comp (ref "C27")
      (value "470nF")
      (footprint "eagle-import:C0603")
      (libsource (lib "eagle-import") (part "C-EUC0603"))
    )
    (comp (ref "C28")
      (value "470nF")
      (footprint "eagle-import:C0603")
      (libsource (lib "eagle-import") (part "C-EUC0603"))
    )
    (comp (ref "C29")
      (value "470nF")
      (footprint "eagle-import:C0603")
      (libsource (lib "eagle-import") (part "C-EUC0603"))
    )
    (comp (ref "C30")
      (value "470nF")
      (footprint "eagle-import:C0603")
      (libsource (lib "eagle-import") (part "C-EUC0603"))
    )
    (comp (ref "C36")
      (value "10nF")
      (footprint "eagle-import:C0603")
      (libsource (lib "eagle-import") (part "C-EUC0603"))
    )
    (comp (ref "C37")
      (value "2.2uF")
      (footprint "eagle-import:C0603")
      (libsource (lib "eagle-import") (part "C-EUC0603"))
    )
    (comp (ref "C40")
      (value "2.2uF")
      (footprint "eagle-import:C0603")
      (libsource (lib "eagle-import") (part "C-EUC0603"))
    )
    (comp (ref "C41")
      (value "470nF")
      (footprint "eagle-import:C0603")
      (libsource (lib "eagle-import") (part "C-EUC0603"))
    )
    (comp (ref "C42")
      (value "470nF")
      (footprint "eagle-import:C0603")
      (libsource (lib "eagle-import") (part "C-EUC0603"))
    )
    (comp (ref "C43")
      (value "470nF")
      (footprint "eagle-import:C0603")
      (libsource (lib "eagle-import") (part "C-EUC0603"))
    )
    (comp (ref "IC2")
      (value "TPS73033DBV-1135395")
      (footprint "eagle-import:SOT23-DBV")
      (libsource (lib "eagle-import") (part "TPS73033DBV"))
    )
    (comp (ref "IC3")
      (value "LD6806TD/12H-2095494")
      (footprint "eagle-import:SOT23-DBV")
      (libsource (lib "eagle-import") (part "LD6806TD/12H"))
    )
    (comp (ref "IC4")
      (value "H57V2562GTR-75C-1907383")
      (footprint "eagle-import:TSOP54-400")
      (libsource (lib "eagle-import") (part "MT48LC64M4A2"))
    )
    (comp (ref "IC6")
      (value "TPS73033DBV-1135395")
      (footprint "eagle-import:SOT23-DBV")
      (libsource (lib "eagle-import") (part "TPS73033DBV"))
    )
    (comp (ref "L1")
      (value "100nH")
      (footprint "eagle-import:R0805")
      (libsource (lib "eagle-import") (part "R-US_R0805"))
    )
    (comp (ref "L2")
      (value "100nH")
      (footprint "eagle-import:R0805")
      (libsource (lib "eagle-import") (part "R-US_R0805"))
    )
    (comp (ref "L3")
      (value "100nH")
      (footprint "eagle-import:R0805")
      (libsource (lib "eagle-import") (part "R-US_R0805"))
    )
    (comp (ref "R7")
      (value "330k")
      (footprint "eagle-import:R0603")
      (libsource (lib "eagle-import") (part "R-EU_R0603"))
    )
    (comp (ref "TP3")
      (value "TPTP15R")
      (footprint "eagle-import:TP15R")
      (libsource (lib "eagle-import") (part "TPTP15R"))
    )
    (comp (ref "TP8")
      (value "TPTP15R")
      (footprint "eagle-import:TP15R")
      (libsource (lib "eagle-import") (part "TPTP15R"))
    )
    (comp (ref "TP9")
      (value "TPTP15R")
      (footprint "eagle-import:TP15R")
      (libsource (lib "eagle-import") (part "TPTP15R"))
    )
    (comp (ref "TP10")
      (value "TPTP15R")
      (footprint "eagle-import:TP15R")
      (libsource (lib "eagle-import") (part "TPTP15R"))
    )
    (comp (ref "IC1")
      (value "XC6SLX9-1876228")
      (footprint "eagle-import:TQG144")
      (libsource (lib "eagle-import") (part "XC6SLX4TQG144-2"))
    )
    (comp (ref "TP13")
      (value "TPTP20R")
      (footprint "eagle-import:TP20R")
      (libsource (lib "eagle-import") (part "TPTP20R"))
    )
    (comp (ref "TP14")
      (value "TPTP20R")
      (footprint "eagle-import:TP20R")
      (libsource (lib "eagle-import") (part "TPTP20R"))
    )
    (comp (ref "TP15")
      (value "TPTP20R")
      (footprint "eagle-import:TP20R")
      (libsource (lib "eagle-import") (part "TPTP20R"))
    )
    (comp (ref "TP16")
      (value "TPTP20R")
      (footprint "eagle-import:TP20R")
      (libsource (lib "eagle-import") (part "TPTP20R"))
    )
    (comp (ref "C38")
      (value "470nF")
      (footprint "eagle-import:C0603")
      (libsource (lib "eagle-import") (part "C-EUC0603"))
    )
    (comp (ref "C39")
      (value "10nF")
      (footprint "eagle-import:C0603")
      (libsource (lib "eagle-import") (part "C-EUC0603"))
    )
    (comp (ref "IC5")
      (value "M25P40-2253716")
      (footprint "eagle-import:SO8")
      (libsource (lib "eagle-import") (part "FLASH"))
    )
    (comp (ref "LED5")
      (value "RED-2099221")
      (footprint "eagle-import:CHIPLED_0603")
      (libsource (lib "eagle-import") (part "LEDCHIPLED_0603"))
    )
    (comp (ref "Q1")
      (value "PDTC123-1757992")
      (footprint "eagle-import:SOT323")
      (libsource (lib "eagle-import") (part "NPN-BIAS-SOT323-BEC"))
    )
    (comp (ref "Q2")
      (value "BC807W")
      (footprint "eagle-import:SOT323-BEC")
      (libsource (lib "eagle-import") (part "BC807W"))
    )
    (comp (ref "Q3")
      (value "PDTC123-1757992")
      (footprint "eagle-import:SOT323")
      (libsource (lib "eagle-import") (part "NPN-BIAS-SOT323-BEC"))
    )
    (comp (ref "Q4")
      (value "BC807W")
      (footprint "eagle-import:SOT323-BEC")
      (libsource (lib "eagle-import") (part "BC807W"))
    )
    (comp (ref "R5")
      (value "330k")
      (footprint "eagle-import:R0603")
      (libsource (lib "eagle-import") (part "R-EU_R0603"))
    )
    (comp (ref "R6")
      (value "4k7")
      (footprint "eagle-import:R0603")
      (libsource (lib "eagle-import") (part "R-EU_R0603"))
    )
    (comp (ref "R59")
      (value "68")
      (footprint "eagle-import:R0603")
      (libsource (lib "eagle-import") (part "R-EU_R0603"))
    )
    (comp (ref "R60")
      (value "6k8 1%")
      (footprint "eagle-import:R0603")
      (libsource (lib "eagle-import") (part "R-EU_R0603"))
    )
    (comp (ref "R61")
      (value "6k8 1%")
      (footprint "eagle-import:R0603")
      (libsource (lib "eagle-import") (part "R-EU_R0603"))
    )
    (comp (ref "R62")
      (value "6k8 1%")
      (footprint "eagle-import:R0603")
      (libsource (lib "eagle-import") (part "R-EU_R0603"))
    )
    (comp (ref "R63")
      (value "4k7 1%")
      (footprint "eagle-import:R0603")
      (libsource (lib "eagle-import") (part "R-EU_R0603"))
    )
    (comp (ref "TP1")
      (value "TPTP15R")
      (footprint "eagle-import:TP15R")
      (libsource (lib "eagle-import") (part "TPTP15R"))
    )
    (comp (ref "TP2")
      (value "TPTP20R")
      (footprint "eagle-import:TP20R")
      (libsource (lib "eagle-import") (part "TPTP20R"))
    )
    (comp (ref "U$1")
      (value "PIC10F320-2074912")
      (footprint "eagle-import:SOT23")
      (libsource (lib "eagle-import") (part "PIC10F320"))
    )
  )
  (nets
    (net (code "1") (name "+3V3") (class "Default")
      (node (ref "C13") (pin "1") (pinfunction "1_1") (pintype "passive"))
      (node (ref "C14") (pin "1") (pinfunction "1_1") (pintype "passive"))
      (node (ref "C15") (pin "1") (pinfunction "1_1") (pintype "passive"))
      (node (ref "C16") (pin "1") (pinfunction "1_1") (pintype "passive"))
      (node (ref "C17") (pin "1") (pinfunction "1_1") (pintype "passive"))
      (node (ref "C21") (pin "1") (pinfunction "1_1") (pintype "passive"))
      (node (ref "C22") (pin "1") (pinfunction "1_1") (pintype "passive"))
      (node (ref "C23") (pin "1") (pinfunction "1_1") (pintype "passive"))
      (node (ref "C24") (pin "1") (pinfunction "1_1") (pintype "passive"))
      (node (ref "C25") (pin "1") (pinfunction "1_1") (pintype "passive"))
      (node (ref "C26") (pin "1") (pinfunction "1_1") (pintype "passive"))
      (node (ref "C27") (pin "1") (pinfunction "1_1") (pintype "passive"))
      (node (ref "C28") (pin "1") (pinfunction "1_1") (pintype "passive"))
      (node (ref "C29") (pin "1") (pinfunction "1_1") (pintype "passive"))
      (node (ref "C30") (pin "1") (pinfunction "1_1") (pintype "passive"))
      (node (ref "C31") (pin "1") (pinfunction "1_1") (pintype "passive"))
      (node (ref "C32") (pin "1") (pinfunction "1_1") (pintype "passive"))
      (node (ref "C33") (pin "1") (pinfunction "1_1") (pintype "passive"))
      (node (ref "C38") (pin "1") (pinfunction "1_1") (pintype "passive"))
      (node (ref "IC1") (pin "103") (pinfunction "VCCO_1_103") (pintype "power_in"))
      (node (ref "IC1") (pin "122") (pinfunction "VCC_0_122") (pintype "power_in"))
      (node (ref "IC1") (pin "125") (pinfunction "VCC_0_125") (pintype "power_in"))
      (node (ref "IC1") (pin "135") (pinfunction "VCC_0_135") (pintype "power_in"))
      (node (ref "IC1") (pin "144") (pinfunction "IO_L1P_HSWAPEN_0_144") (pintype "bidirectional"))
      (node (ref "IC1") (pin "18") (pinfunction "VCCO_3_18") (pintype "power_in"))
      (node (ref "IC1") (pin "31") (pinfunction "VCCO_3_31") (pintype "power_in"))
      (node (ref "IC1") (pin "4") (pinfunction "VCCO_3_4") (pintype "power_in"))
      (node (ref "IC1") (pin "42") (pinfunction "VCCO_2_42") (pintype "power_in"))
      (node (ref "IC1") (pin "63") (pinfunction "VCCO_2_63") (pintype "power_in"))
      (node (ref "IC1") (pin "69") (pinfunction "IO_L1N_M0_CMPMISO_2_69") (pintype "bidirectional"))
      (node (ref "IC1") (pin "76") (pinfunction "VCCO_1_76") (pintype "power_in"))
      (node (ref "IC1") (pin "86") (pinfunction "VCCO_1_86") (pintype "power_in"))
      (node (ref "IC5") (pin "3") (pinfunction "WP_(IO2)_3") (pintype "bidirectional"))
      (node (ref "IC5") (pin "7") (pinfunction "HOLD_(IO3)_7") (pintype "bidirectional"))
      (node (ref "IC5") (pin "8") (pinfunction "VCC_8") (pintype "power_in"))
      (node (ref "L3") (pin "2") (pinfunction "2_2") (pintype "passive"))
      (node (ref "Q4") (pin "2") (pinfunction "E_2") (pintype "passive"))
      (node (ref "R10") (pin "1") (pinfunction "1_1") (pintype "passive"))
      (node (ref "R5") (pin "2") (pinfunction "2_2") (pintype "passive"))
      (node (ref "R6") (pin "2") (pinfunction "2_2") (pintype "passive"))
      (node (ref "TR1") (pin "1") (pinfunction "VCCA_1") (pintype "passive"))
      (node (ref "TR10") (pin "1") (pinfunction "VCCA_1") (pintype "passive"))
      (node (ref "TR11") (pin "1") (pinfunction "VCCA_1") (pintype "passive"))
      (node (ref "TR12") (pin "1") (pinfunction "VCCA_1") (pintype "passive"))
      (node (ref "TR13") (pin "1") (pinfunction "VCCA_1") (pintype "passive"))
      (node (ref "TR14") (pin "1") (pinfunction "VCCA_1") (pintype "passive"))
      (node (ref "TR15") (pin "1") (pinfunction "VCCA_1") (pintype "passive"))
      (node (ref "TR16") (pin "1") (pinfunction "VCCA_1") (pintype "passive"))
      (node (ref "TR2") (pin "1") (pinfunction "VCCA_1") (pintype "passive"))
      (node (ref "TR3") (pin "1") (pinfunction "VCCA_1") (pintype "passive"))
      (node (ref "TR4") (pin "1") (pinfunction "VCCA_1") (pintype "passive"))
      (node (ref "TR5") (pin "1") (pinfunction "VCCA_1") (pintype "passive"))
      (node (ref "TR6") (pin "1") (pinfunction "VCCA_1") (pintype "passive"))
      (node (ref "TR7") (pin "1") (pinfunction "VCCA_1") (pintype "passive"))
      (node (ref "TR8") (pin "1") (pinfunction "VCCA_1") (pintype "passive"))
      (node (ref "TR9") (pin "1") (pinfunction "VCCA_1") (pintype "passive"))
      (node (ref "U$1") (pin "5") (pinfunction "VCC_5") (pintype "passive"))
      (node (ref "X2") (pin "1") (pinfunction "EN_1") (pintype "bidirectional"))
      (node (ref "X2") (pin "4") (pinfunction "VCC_4") (pintype "passive"))
    )
    (net (code "2") (name "+5V") (class "Default")
      (node (ref "C40") (pin "1") (pinfunction "1_1") (pintype "passive"))
      (node (ref "C6") (pin "1") (pinfunction "1_1") (pintype "passive"))
      (node (ref "IC2") (pin "1") (pinfunction "IN_1") (pintype "passive"))
      (node (ref "IC2") (pin "3") (pinfunction "EN_3") (pintype "input"))
      (node (ref "IC3") (pin "1") (pinfunction "IN_1") (pintype "passive"))
      (node (ref "IC3") (pin "3") (pinfunction "EN_3") (pintype "input"))
      (node (ref "IC6") (pin "1") (pinfunction "IN_1") (pintype "passive"))
      (node (ref "JP10") (pin "1") (pinfunction "1_1") (pintype "passive"))
      (node (ref "JP9") (pin "1") (pinfunction "1_1") (pintype "passive"))
      (node (ref "Q2") (pin "2") (pinfunction "E_2") (pintype "passive"))
      (node (ref "TP10") (pin "TP") (pinfunction "TP_TP") (pintype "input"))
      (node (ref "X1") (pin "1") (pinfunction "VBUS_1") (pintype "passive"))
    )
    (net (code "3") (name "AD_RA0") (class "Default")
      (node (ref "IC1") (pin "46") (pinfunction "IO_L49P_D3_2_46") (pintype "bidirectional"))
      (node (ref "U$1") (pin "1") (pinfunction "ICSPDAT/RA0_1") (pintype "bidirectional"))
    )
    (net (code "4") (name "AD_RA1") (class "Default")
      (node (ref "IC1") (pin "47") (pinfunction "IO_L48N_RDWR_B_VREF_2_47") (pintype "bidirectional"))
      (node (ref "U$1") (pin "3") (pinfunction "ICSPCLK/RA1_3") (pintype "bidirectional"))
    )
    (net (code "5") (name "AD_RA3") (class "Default")
      (node (ref "IC1") (pin "51") (pinfunction "IO_L31P_GCLK31_D14_2_51") (pintype "bidirectional"))
      (node (ref "U$1") (pin "6") (pinfunction "MCLRB/VPP/RA3_6") (pintype "input"))
    )
    (net (code "6") (name "CFG_DONE") (class "Default")
      (node (ref "IC1") (pin "71") (pinfunction "DONE_2_71") (pintype "bidirectional"))
      (node (ref "R59") (pin "1") (pinfunction "1_1") (pintype "passive"))
    )
    (net (code "7") (name "CLK_33") (class "Default")
      (node (ref "IC1") (pin "134") (pinfunction "IO_L34P_GCLK19_0_134") (pintype "bidirectional"))
      (node (ref "X2") (pin "3") (pinfunction "OUT_3") (pintype "output"))
    )
    (net (code "8") (name "FLASH_CLK") (class "Default")
      (node (ref "IC1") (pin "70") (pinfunction "IO_L1P_CCLK_2_70") (pintype "bidirectional"))
      (node (ref "IC5") (pin "6") (pinfunction "CLK_6") (pintype "input"))
    )
    (net (code "9") (name "FLASH_CS") (class "Default")
      (node (ref "IC1") (pin "38") (pinfunction "IO_L65N_CSO_B_2_38") (pintype "bidirectional"))
      (node (ref "IC5") (pin "1") (pinfunction "CS_1") (pintype "input"))
      (node (ref "R5") (pin "1") (pinfunction "1_1") (pintype "passive"))
    )
    (net (code "10") (name "FLASH_SI") (class "Default")
      (node (ref "IC1") (pin "64") (pinfunction "IO_L3N_MOSI_CSI_B_MISO0_2_64") (pintype "bidirectional"))
      (node (ref "IC5") (pin "5") (pinfunction "SI_(IO0)_5") (pintype "bidirectional"))
    )
    (net (code "11") (name "FLASH_SO") (class "Default")
      (node (ref "IC1") (pin "65") (pinfunction "IO_L3P_D0_DIN_MISO_MISO1_2_65") (pintype "bidirectional"))
      (node (ref "IC5") (pin "2") (pinfunction "SO_(IO1)_2") (pintype "output"))
    )
    (net (code "12") (name "GND") (class "Default")
      (node (ref "C1") (pin "2") (pinfunction "2_2") (pintype "passive"))
      (node (ref "C10") (pin "2") (pinfunction "2_2") (pintype "passive"))
      (node (ref "C11") (pin "2") (pinfunction "2_2") (pintype "passive"))
      (node (ref "C12") (pin "2") (pinfunction "2_2") (pintype "passive"))
      (node (ref "C13") (pin "2") (pinfunction "2_2") (pintype "passive"))
      (node (ref "C14") (pin "2") (pinfunction "2_2") (pintype "passive"))
      (node (ref "C15") (pin "2") (pinfunction "2_2") (pintype "passive"))
      (node (ref "C16") (pin "2") (pinfunction "2_2") (pintype "passive"))
      (node (ref "C17") (pin "2") (pinfunction "2_2") (pintype "passive"))
      (node (ref "C18") (pin "2") (pinfunction "2_2") (pintype "passive"))
      (node (ref "C19") (pin "2") (pinfunction "2_2") (pintype "passive"))
      (node (ref "C2") (pin "2") (pinfunction "2_2") (pintype "passive"))
      (node (ref "C20") (pin "2") (pinfunction "2_2") (pintype "passive"))
      (node (ref "C21") (pin "2") (pinfunction "2_2") (pintype "passive"))
      (node (ref "C22") (pin "2") (pinfunction "2_2") (pintype "passive"))
      (node (ref "C23") (pin "2") (pinfunction "2_2") (pintype "passive"))
      (node (ref "C24") (pin "2") (pinfunction "2_2") (pintype "passive"))
      (node (ref "C25") (pin "2") (pinfunction "2_2") (pintype "passive"))
      (node (ref "C26") (pin "2") (pinfunction "2_2") (pintype "passive"))
      (node (ref "C27") (pin "2") (pinfunction "2_2") (pintype "passive"))
      (node (ref "C28") (pin "2") (pinfunction "2_2") (pintype "passive"))
      (node (ref "C29") (pin "2") (pinfunction "2_2") (pintype "passive"))
      (node (ref "C3") (pin "2") (pinfunction "2_2") (pintype "passive"))
      (node (ref "C30") (pin "2") (pinfunction "2_2") (pintype "passive"))
      (node (ref "C31") (pin "2") (pinfunction "2_2") (pintype "passive"))
      (node (ref "C32") (pin "2") (pinfunction "2_2") (pintype "passive"))
      (node (ref "C33") (pin "2") (pinfunction "2_2") (pintype "passive"))
      (node (ref "C34") (pin "2") (pinfunction "2_2") (pintype "passive"))
      (node (ref "C35") (pin "2") (pinfunction "2_2") (pintype "passive"))
      (node (ref "C36") (pin "2") (pinfunction "2_2") (pintype "passive"))
      (node (ref "C37") (pin "2") (pinfunction "2_2") (pintype "passive"))
      (node (ref "C38") (pin "2") (pinfunction "2_2") (pintype "passive"))
      (node (ref "C39") (pin "2") (pinfunction "2_2") (pintype "passive"))
      (node (ref "C4") (pin "2") (pinfunction "2_2") (pintype "passive"))
      (node (ref "C40") (pin "2") (pinfunction "2_2") (pintype "passive"))
      (node (ref "C41") (pin "2") (pinfunction "2_2") (pintype "passive"))
      (node (ref "C42") (pin "2") (pinfunction "2_2") (pintype "passive"))
      (node (ref "C43") (pin "2") (pinfunction "2_2") (pintype "passive"))
      (node (ref "C5") (pin "2") (pinfunction "2_2") (pintype "passive"))
      (node (ref "C6") (pin "2") (pinfunction "2_2") (pintype "passive"))
      (node (ref "C7") (pin "2") (pinfunction "2_2") (pintype "passive"))
      (node (ref "C8") (pin "2") (pinfunction "2_2") (pintype "passive"))
      (node (ref "C9") (pin "2") (pinfunction "2_2") (pintype "passive"))
      (node (ref "IC1") (pin "108") (pinfunction "GND_108") (pintype "power_in"))
      (node (ref "IC1") (pin "113") (pinfunction "GND_113") (pintype "power_in"))
      (node (ref "IC1") (pin "13") (pinfunction "GND_13") (pintype "power_in"))
      (node (ref "IC1") (pin "130") (pinfunction "GND_130") (pintype "power_in"))
      (node (ref "IC1") (pin "136") (pinfunction "GND_136") (pintype "power_in"))
      (node (ref "IC1") (pin "25") (pinfunction "GND_25") (pintype "power_in"))
      (node (ref "IC1") (pin "3") (pinfunction "GND_3") (pintype "power_in"))
      (node (ref "IC1") (pin "49") (pinfunction "GND_49") (pintype "power_in"))
      (node (ref "IC1") (pin "54") (pinfunction "GND_54") (pintype "power_in"))
      (node (ref "IC1") (pin "60") (pinfunction "IO_L13P_M1_2_60") (pintype "bidirectional"))
      (node (ref "IC1") (pin "68") (pinfunction "GND_68") (pintype "power_in"))
      (node (ref "IC1") (pin "73") (pinfunction "SUSPEND_73") (pintype "input"))
      (node (ref "IC1") (pin "77") (pinfunction "GND_77") (pintype "power_in"))
      (node (ref "IC1") (pin "91") (pinfunction "GND_91") (pintype "power_in"))
      (node (ref "IC1") (pin "96") (pinfunction "GND_96") (pintype "power_in"))
      (node (ref "IC2") (pin "2") (pinfunction "GND_2") (pintype "passive"))
      (node (ref "IC3") (pin "2") (pinfunction "GND_2") (pintype "passive"))
      (node (ref "IC4") (pin "12") (pinfunction "VSSQ_12") (pintype "power_in"))
      (node (ref "IC4") (pin "28") (pinfunction "VSS_28") (pintype "power_in"))
      (node (ref "IC4") (pin "41") (pinfunction "VSS_41") (pintype "power_in"))
      (node (ref "IC4") (pin "46") (pinfunction "VSSQ_46") (pintype "power_in"))
      (node (ref "IC4") (pin "52") (pinfunction "VSSQ_52") (pintype "power_in"))
      (node (ref "IC4") (pin "54") (pinfunction "VSS_54") (pintype "power_in"))
      (node (ref "IC4") (pin "6") (pinfunction "VSSQ_6") (pintype "power_in"))
      (node (ref "IC5") (pin "4") (pinfunction "GND_4") (pintype "passive"))
      (node (ref "IC6") (pin "2") (pinfunction "GND_2") (pintype "passive"))
      (node (ref "JP5") (pin "1") (pinfunction "1_1") (pintype "passive"))
      (node (ref "JP6") (pin "1") (pinfunction "1_1") (pintype "passive"))
      (node (ref "JP7") (pin "1") (pinfunction "1_1") (pintype "passive"))
      (node (ref "JP8") (pin "1") (pinfunction "1_1") (pintype "passive"))
      (node (ref "LED1") (pin "C") (pinfunction "C_C") (pintype "passive"))
      (node (ref "LED2") (pin "C") (pinfunction "C_C") (pintype "passive"))
      (node (ref "LED3") (pin "C") (pinfunction "C_C") (pintype "passive"))
      (node (ref "LED4") (pin "C") (pinfunction "C_C") (pintype "passive"))
      (node (ref "LED5") (pin "C") (pinfunction "C_C") (pintype "passive"))
      (node (ref "Q1") (pin "2") (pinfunction "E_2") (pintype "passive"))
      (node (ref "Q3") (pin "2") (pinfunction "E_2") (pintype "passive"))
      (node (ref "R27") (pin "1") (pinfunction "1_1") (pintype "passive"))
      (node (ref "R28") (pin "1") (pinfunction "1_1") (pintype "passive"))
      (node (ref "R29") (pin "1") (pinfunction "1_1") (pintype "passive"))
      (node (ref "R30") (pin "1") (pinfunction "1_1") (pintype "passive"))
      (node (ref "R31") (pin "1") (pinfunction "1_1") (pintype "passive"))
      (node (ref "R32") (pin "1") (pinfunction "1_1") (pintype "passive"))
      (node (ref "R33") (pin "1") (pinfunction "1_1") (pintype "passive"))
      (node (ref "R34") (pin "1") (pinfunction "1_1") (pintype "passive"))
      (node (ref "R35") (pin "1") (pinfunction "1_1") (pintype "passive"))
      (node (ref "R36") (pin "1") (pinfunction "1_1") (pintype "passive"))
      (node (ref "R37") (pin "1") (pinfunction "1_1") (pintype "passive"))
      (node (ref "R38") (pin "1") (pinfunction "1_1") (pintype "passive"))
      (node (ref "R39") (pin "1") (pinfunction "1_1") (pintype "passive"))
      (node (ref "R40") (pin "1") (pinfunction "1_1") (pintype "passive"))
      (node (ref "R41") (pin "1") (pinfunction "1_1") (pintype "passive"))
      (node (ref "R42") (pin "1") (pinfunction "1_1") (pintype "passive"))
      (node (ref "R43") (pin "1") (pinfunction "1_1") (pintype "passive"))
      (node (ref "R44") (pin "1") (pinfunction "1_1") (pintype "passive"))
      (node (ref "R45") (pin "1") (pinfunction "1_1") (pintype "passive"))
      (node (ref "R46") (pin "1") (pinfunction "1_1") (pintype "passive"))
      (node (ref "R47") (pin "1") (pinfunction "1_1") (pintype "passive"))
      (node (ref "R48") (pin "1") (pinfunction "1_1") (pintype "passive"))
      (node (ref "R49") (pin "1") (pinfunction "1_1") (pintype "passive"))
      (node (ref "R50") (pin "1") (pinfunction "1_1") (pintype "passive"))
      (node (ref "R51") (pin "1") (pinfunction "1_1") (pintype "passive"))
      (node (ref "R52") (pin "1") (pinfunction "1_1") (pintype "passive"))
      (node (ref "R53") (pin "1") (pinfunction "1_1") (pintype "passive"))
      (node (ref "R54") (pin "1") (pinfunction "1_1") (pintype "passive"))
      (node (ref "R55") (pin "1") (pinfunction "1_1") (pintype "passive"))
      (node (ref "R56") (pin "1") (pinfunction "1_1") (pintype "passive"))
      (node (ref "R57") (pin "1") (pinfunction "1_1") (pintype "passive"))
      (node (ref "R58") (pin "1") (pinfunction "1_1") (pintype "passive"))
      (node (ref "R62") (pin "1") (pinfunction "1_1") (pintype "passive"))
      (node (ref "R7") (pin "1") (pinfunction "1_1") (pintype "passive"))
      (node (ref "TP2") (pin "TP") (pinfunction "TP_TP") (pintype "input"))
      (node (ref "TR1") (pin "2") (pinfunction "GND_2") (pintype "passive"))
      (node (ref "TR10") (pin "2") (pinfunction "GND_2") (pintype "passive"))
      (node (ref "TR11") (pin "2") (pinfunction "GND_2") (pintype "passive"))
      (node (ref "TR12") (pin "2") (pinfunction "GND_2") (pintype "passive"))
      (node (ref "TR13") (pin "2") (pinfunction "GND_2") (pintype "passive"))
      (node (ref "TR14") (pin "2") (pinfunction "GND_2") (pintype "passive"))
      (node (ref "TR15") (pin "2") (pinfunction "GND_2") (pintype "passive"))
      (node (ref "TR16") (pin "2") (pinfunction "GND_2") (pintype "passive"))
      (node (ref "TR2") (pin "2") (pinfunction "GND_2") (pintype "passive"))
      (node (ref "TR3") (pin "2") (pinfunction "GND_2") (pintype "passive"))
      (node (ref "TR4") (pin "2") (pinfunction "GND_2") (pintype "passive"))
      (node (ref "TR5") (pin "2") (pinfunction "GND_2") (pintype "passive"))
      (node (ref "TR6") (pin "2") (pinfunction "GND_2") (pintype "passive"))
      (node (ref "TR7") (pin "2") (pinfunction "GND_2") (pintype "passive"))
      (node (ref "TR8") (pin "2") (pinfunction "GND_2") (pintype "passive"))
      (node (ref "TR9") (pin "2") (pinfunction "GND_2") (pintype "passive"))
      (node (ref "U$1") (pin "2") (pinfunction "GND_2") (pintype "passive"))
      (node (ref "X1") (pin "5") (pinfunction "GND_5") (pintype "passive"))
      (node (ref "X2") (pin "2") (pinfunction "GND_2") (pintype "passive"))
    )
    (net (code "13") (name "LED1") (class "Default")
      (node (ref "IC1") (pin "139") (pinfunction "IO_L3N_0_139") (pintype "bidirectional"))
      (node (ref "R4") (pin "1") (pinfunction "1_1") (pintype "passive"))
    )
    (net (code "14") (name "LED2") (class "Default")
      (node (ref "IC1") (pin "138") (pinfunction "IO_L4P_0_138") (pintype "bidirectional"))
      (node (ref "R8") (pin "1") (pinfunction "1_1") (pintype "passive"))
    )
    (net (code "15") (name "LED3") (class "Default")
      (node (ref "IC1") (pin "133") (pinfunction "IO_L34N_GCLK18_0_133") (pintype "bidirectional"))
      (node (ref "R9") (pin "1") (pinfunction "1_1") (pintype "passive"))
    )
    (net (code "16") (name "M_A0") (class "Default")
      (node (ref "IC1") (pin "79") (pinfunction "IO_L47P_1_79") (pintype "bidirectional"))
      (node (ref "IC4") (pin "23") (pinfunction "A0_23") (pintype "input"))
    )
    (net (code "17") (name "M_A1") (class "Default")
      (node (ref "IC1") (pin "78") (pinfunction "IO_L47N_1_78") (pintype "bidirectional"))
      (node (ref "IC4") (pin "24") (pinfunction "A1_24") (pintype "input"))
    )
    (net (code "18") (name "M_A2") (class "Default")
      (node (ref "IC1") (pin "75") (pinfunction "IO_L74P_AWAKE_1_75") (pintype "bidirectional"))
      (node (ref "IC4") (pin "25") (pinfunction "A2_25") (pintype "input"))
    )
    (net (code "19") (name "M_A3") (class "Default")
      (node (ref "IC1") (pin "74") (pinfunction "IO_L74N_DOUT_BUSY_1_74") (pintype "bidirectional"))
      (node (ref "IC4") (pin "26") (pinfunction "A3_26") (pintype "input"))
    )
    (net (code "20") (name "M_A4") (class "Default")
      (node (ref "IC1") (pin "132") (pinfunction "IO_L35P_GCLK17_0_132") (pintype "bidirectional"))
      (node (ref "IC4") (pin "29") (pinfunction "A4_29") (pintype "input"))
    )
    (net (code "21") (name "M_A5") (class "Default")
      (node (ref "IC1") (pin "102") (pinfunction "IO_L32P_1_102") (pintype "bidirectional"))
      (node (ref "IC4") (pin "30") (pinfunction "A5_30") (pintype "input"))
    )
    (net (code "22") (name "M_A6") (class "Default")
      (node (ref "IC1") (pin "104") (pinfunction "IO_L1N_VREF_1_104") (pintype "bidirectional"))
      (node (ref "IC4") (pin "31") (pinfunction "A6_31") (pintype "input"))
    )
    (net (code "23") (name "M_A7") (class "Default")
      (node (ref "IC1") (pin "131") (pinfunction "IO_L35N_GCLK16_0_131") (pintype "bidirectional"))
      (node (ref "IC4") (pin "32") (pinfunction "A7_32") (pintype "input"))
    )
    (net (code "24") (name "M_A8") (class "Default")
      (node (ref "IC1") (pin "127") (pinfunction "IO_L36P_GCLK15_0_127") (pintype "bidirectional"))
      (node (ref "IC4") (pin "33") (pinfunction "A8_33") (pintype "input"))
    )
    (net (code "25") (name "M_A9") (class "Default")
      (node (ref "IC1") (pin "126") (pinfunction "IO_L36N_GCLK14_0_126") (pintype "bidirectional"))
      (node (ref "IC4") (pin "34") (pinfunction "A9_34") (pintype "input"))
    )
    (net (code "26") (name "M_A10") (class "Default")
      (node (ref "IC1") (pin "80") (pinfunction "IO_L46N_1_80") (pintype "bidirectional"))
      (node (ref "IC4") (pin "22") (pinfunction "A10_22") (pintype "input"))
    )
    (net (code "27") (name "M_A11") (class "Default")
      (node (ref "IC1") (pin "124") (pinfunction "IO_L37P_GCLK13_0_124") (pintype "bidirectional"))
      (node (ref "IC4") (pin "35") (pinfunction "A11_35") (pintype "input"))
    )
    (net (code "28") (name "M_A12") (class "Default")
      (node (ref "IC1") (pin "123") (pinfunction "IO_L37N_GCLK12_0_123") (pintype "bidirectional"))
      (node (ref "IC4") (pin "36") (pinfunction "A12_36") (pintype "input"))
    )
    (net (code "29") (name "M_BA0") (class "Default")
      (node (ref "IC1") (pin "82") (pinfunction "IO_L45N_1_82") (pintype "bidirectional"))
      (node (ref "IC4") (pin "20") (pinfunction "BA0_20") (pintype "input"))
    )
    (net (code "30") (name "M_BA1") (class "Default")
      (node (ref "IC1") (pin "81") (pinfunction "IO_L46P_1_81") (pintype "bidirectional"))
      (node (ref "IC4") (pin "21") (pinfunction "BA1_21") (pintype "input"))
    )
    (net (code "31") (name "M_CAS") (class "Default")
      (node (ref "IC1") (pin "85") (pinfunction "IO_L43P_GCLK5_1_85") (pintype "bidirectional"))
      (node (ref "IC4") (pin "17") (pinfunction "~{CAS}_17") (pintype "input"))
    )
    (net (code "32") (name "M_CKE") (class "Default")
      (node (ref "IC1") (pin "121") (pinfunction "IO_L62P_0_121") (pintype "bidirectional"))
      (node (ref "IC4") (pin "37") (pinfunction "CKE_37") (pintype "input"))
    )
    (net (code "33") (name "M_CLK") (class "Default")
      (node (ref "IC1") (pin "105") (pinfunction "IO_L1P_1_105") (pintype "bidirectional"))
      (node (ref "IC4") (pin "38") (pinfunction "CLK_38") (pintype "input"))
    )
    (net (code "34") (name "M_CS") (class "Default")
      (node (ref "IC1") (pin "83") (pinfunction "IO_L45P_1_83") (pintype "bidirectional"))
      (node (ref "IC4") (pin "19") (pinfunction "\\CS_19") (pintype "input"))
    )
    (net (code "35") (name "M_DQ0") (class "Default")
      (node (ref "IC1") (pin "92") (pinfunction "IO_L41N_GCLK8_1_92") (pintype "bidirectional"))
      (node (ref "IC4") (pin "2") (pinfunction "DQ0_2") (pintype "tri_state"))
    )
    (net (code "36") (name "M_DQ1") (class "Default")
      (node (ref "IC1") (pin "93") (pinfunction "IO_L41P_GCLK9_IRDY1_1_93") (pintype "bidirectional"))
      (node (ref "IC4") (pin "4") (pinfunction "DQ1_4") (pintype "tri_state"))
    )
    (net (code "37") (name "M_DQ2") (class "Default")
      (node (ref "IC1") (pin "94") (pinfunction "IO_L40N_GCLK10_1_94") (pintype "bidirectional"))
      (node (ref "IC4") (pin "5") (pinfunction "DQ2_5") (pintype "tri_state"))
    )
    (net (code "38") (name "M_DQ3") (class "Default")
      (node (ref "IC1") (pin "95") (pinfunction "IO_L40P_GCLK11_1_95") (pintype "bidirectional"))
      (node (ref "IC4") (pin "7") (pinfunction "DQ3_7") (pintype "tri_state"))
    )
    (net (code "39") (name "M_DQ4") (class "Default")
      (node (ref "IC1") (pin "97") (pinfunction "IO_L34N_1_97") (pintype "bidirectional"))
      (node (ref "IC4") (pin "8") (pinfunction "DQ4_8") (pintype "tri_state"))
    )
    (net (code "40") (name "M_DQ5") (class "Default")
      (node (ref "IC1") (pin "98") (pinfunction "IO_L34P_1_98") (pintype "bidirectional"))
      (node (ref "IC4") (pin "10") (pinfunction "DQ5_10") (pintype "tri_state"))
    )
    (net (code "41") (name "M_DQ6") (class "Default")
      (node (ref "IC1") (pin "99") (pinfunction "IO_L33N_1_99") (pintype "bidirectional"))
      (node (ref "IC4") (pin "11") (pinfunction "DQ6_11") (pintype "tri_state"))
    )
    (net (code "42") (name "M_DQ7") (class "Default")
      (node (ref "IC1") (pin "100") (pinfunction "IO_L33P_1_100") (pintype "bidirectional"))
      (node (ref "IC4") (pin "13") (pinfunction "DQ7_13") (pintype "tri_state"))
    )
    (net (code "43") (name "M_DQ8") (class "Default")
      (node (ref "IC1") (pin "119") (pinfunction "IO_L63P_SCP7_0_119") (pintype "bidirectional"))
      (node (ref "IC4") (pin "42") (pinfunction "DQ8_42") (pintype "tri_state"))
    )
    (net (code "44") (name "M_DQ9") (class "Default")
      (node (ref "IC1") (pin "118") (pinfunction "IO_L63N_SCP6_0_118") (pintype "bidirectional"))
      (node (ref "IC4") (pin "44") (pinfunction "DQ9_44") (pintype "tri_state"))
    )
    (net (code "45") (name "M_DQ10") (class "Default")
      (node (ref "IC1") (pin "117") (pinfunction "IO_L64P_SCP5_0_117") (pintype "bidirectional"))
      (node (ref "IC4") (pin "45") (pinfunction "DQ10_45") (pintype "tri_state"))
    )
    (net (code "46") (name "M_DQ11") (class "Default")
      (node (ref "IC1") (pin "116") (pinfunction "IO_L64N_SCP4_0_116") (pintype "bidirectional"))
      (node (ref "IC4") (pin "47") (pinfunction "DQ11_47") (pintype "tri_state"))
    )
    (net (code "47") (name "M_DQ12") (class "Default")
      (node (ref "IC1") (pin "115") (pinfunction "IO_L65P_SCP3_0_115") (pintype "bidirectional"))
      (node (ref "IC4") (pin "48") (pinfunction "DQ12_48") (pintype "tri_state"))
    )
    (net (code "48") (name "M_DQ13") (class "Default")
      (node (ref "IC1") (pin "114") (pinfunction "IO_L65N_SCP2_0_114") (pintype "bidirectional"))
      (node (ref "IC4") (pin "50") (pinfunction "DQ13_50") (pintype "tri_state"))
    )
    (net (code "49") (name "M_DQ14") (class "Default")
      (node (ref "IC1") (pin "112") (pinfunction "IO_L66P_SCP1_0_112") (pintype "bidirectional"))
      (node (ref "IC4") (pin "51") (pinfunction "DQ14_51") (pintype "tri_state"))
    )
    (net (code "50") (name "M_DQ15") (class "Default")
      (node (ref "IC1") (pin "111") (pinfunction "IO_L66N_SCP0_0_111") (pintype "bidirectional"))
      (node (ref "IC4") (pin "53") (pinfunction "DQ15_53") (pintype "tri_state"))
    )
    (net (code "51") (name "M_DQMH") (class "Default")
      (node (ref "IC1") (pin "120") (pinfunction "IO_L62N_VREF_0_120") (pintype "bidirectional"))
      (node (ref "IC4") (pin "39") (pinfunction "DQMH_39") (pintype "input"))
    )
    (net (code "52") (name "M_DQML") (class "Default")
      (node (ref "IC1") (pin "88") (pinfunction "IO_L42P_GCLK7_1_88") (pintype "bidirectional"))
      (node (ref "IC4") (pin "15") (pinfunction "DQML_15") (pintype "input"))
    )
    (net (code "53") (name "M_PWREN") (class "Default")
      (node (ref "IC1") (pin "101") (pinfunction "IO_L32N_1_101") (pintype "bidirectional"))
      (node (ref "IC6") (pin "3") (pinfunction "EN_3") (pintype "input"))
      (node (ref "R7") (pin "2") (pinfunction "2_2") (pintype "passive"))
    )
    (net (code "54") (name "M_RAS") (class "Default")
      (node (ref "IC1") (pin "84") (pinfunction "IO_L43N_GCLK4_1_84") (pintype "bidirectional"))
      (node (ref "IC4") (pin "18") (pinfunction "~{RAS}_18") (pintype "input"))
    )
    (net (code "55") (name "M_WE") (class "Default")
      (node (ref "IC1") (pin "87") (pinfunction "IO_L42N_GCLK6_TRDY1_1_87") (pintype "bidirectional"))
      (node (ref "IC4") (pin "16") (pinfunction "~{WE}_16") (pintype "input"))
    )
    (net (code "56") (name "Net-(IC2-NR)") (class "Default")
      (node (ref "C1") (pin "1") (pinfunction "1_1") (pintype "passive"))
      (node (ref "IC2") (pin "4") (pinfunction "NR_4") (pintype "passive"))
    )
    (net (code "57") (name "Net-(IC2-OUT)") (class "Default")
      (node (ref "C2") (pin "1") (pinfunction "1_1") (pintype "passive"))
      (node (ref "IC2") (pin "5") (pinfunction "OUT_5") (pintype "passive"))
      (node (ref "L2") (pin "1") (pinfunction "1_1") (pintype "passive"))
      (node (ref "L3") (pin "1") (pinfunction "1_1") (pintype "passive"))
      (node (ref "TP9") (pin "TP") (pinfunction "TP_TP") (pintype "input"))
    )
    (net (code "58") (name "Net-(IC3-OUT)") (class "Default")
      (node (ref "C5") (pin "1") (pinfunction "1_1") (pintype "passive"))
      (node (ref "IC3") (pin "5") (pinfunction "OUT_5") (pintype "passive"))
      (node (ref "L1") (pin "1") (pinfunction "1_1") (pintype "passive"))
      (node (ref "TP8") (pin "TP") (pinfunction "TP_TP") (pintype "input"))
    )
    (net (code "59") (name "Net-(IC6-NR)") (class "Default")
      (node (ref "C36") (pin "1") (pinfunction "1_1") (pintype "passive"))
      (node (ref "IC6") (pin "4") (pinfunction "NR_4") (pintype "passive"))
    )
    (net (code "60") (name "Net-(IC6-OUT)") (class "Default")
      (node (ref "C37") (pin "1") (pinfunction "1_1") (pintype "passive"))
      (node (ref "C41") (pin "1") (pinfunction "1_1") (pintype "passive"))
      (node (ref "C42") (pin "1") (pinfunction "1_1") (pintype "passive"))
      (node (ref "C43") (pin "1") (pinfunction "1_1") (pintype "passive"))
      (node (ref "IC4") (pin "1") (pinfunction "VDD_1") (pintype "power_in"))
      (node (ref "IC4") (pin "14") (pinfunction "VDD_14") (pintype "power_in"))
      (node (ref "IC4") (pin "27") (pinfunction "VDD_27") (pintype "power_in"))
      (node (ref "IC4") (pin "3") (pinfunction "VDDQ_3") (pintype "power_in"))
      (node (ref "IC4") (pin "43") (pinfunction "VDDQ_43") (pintype "power_in"))
      (node (ref "IC4") (pin "49") (pinfunction "VDDQ_49") (pintype "power_in"))
      (node (ref "IC4") (pin "9") (pinfunction "VDDQ_9") (pintype "power_in"))
      (node (ref "IC6") (pin "5") (pinfunction "OUT_5") (pintype "passive"))
      (node (ref "TP3") (pin "TP") (pinfunction "TP_TP") (pintype "input"))
    )
    (net (code "61") (name "Net-(JP97-Pad1)") (class "Default")
      (node (ref "JP97") (pin "1") (pinfunction "1_1") (pintype "passive"))
      (node (ref "JP98") (pin "1") (pinfunction "1_1") (pintype "passive"))
      (node (ref "R19") (pin "2") (pinfunction "2_2") (pintype "passive"))
      (node (ref "R35") (pin "2") (pinfunction "2_2") (pintype "passive"))
    )
    (net (code "62") (name "Net-(JP100-Pad1)") (class "Default")
      (node (ref "JP100") (pin "1") (pinfunction "1_1") (pintype "passive"))
      (node (ref "JP99") (pin "1") (pinfunction "1_1") (pintype "passive"))
      (node (ref "R20") (pin "2") (pinfunction "2_2") (pintype "passive"))
      (node (ref "R36") (pin "2") (pinfunction "2_2") (pintype "passive"))
    )
    (net (code "63") (name "Net-(JP101-Pad1)") (class "Default")
      (node (ref "JP101") (pin "1") (pinfunction "1_1") (pintype "passive"))
      (node (ref "JP102") (pin "1") (pinfunction "1_1") (pintype "passive"))
      (node (ref "R21") (pin "2") (pinfunction "2_2") (pintype "passive"))
      (node (ref "R37") (pin "2") (pinfunction "2_2") (pintype "passive"))
    )
    (net (code "64") (name "Net-(JP103-Pad1)") (class "Default")
      (node (ref "JP103") (pin "1") (pinfunction "1_1") (pintype "passive"))
      (node (ref "JP104") (pin "1") (pinfunction "1_1") (pintype "passive"))
      (node (ref "R22") (pin "2") (pinfunction "2_2") (pintype "passive"))
      (node (ref "R38") (pin "2") (pinfunction "2_2") (pintype "passive"))
    )
    (net (code "65") (name "Net-(JP105-Pad1)") (class "Default")
      (node (ref "JP105") (pin "1") (pinfunction "1_1") (pintype "passive"))
      (node (ref "JP106") (pin "1") (pinfunction "1_1") (pintype "passive"))
      (node (ref "R23") (pin "2") (pinfunction "2_2") (pintype "passive"))
      (node (ref "R39") (pin "2") (pinfunction "2_2") (pintype "passive"))
    )
    (net (code "66") (name "Net-(JP107-Pad1)") (class "Default")
      (node (ref "JP107") (pin "1") (pinfunction "1_1") (pintype "passive"))
      (node (ref "JP108") (pin "1") (pinfunction "1_1") (pintype "passive"))
      (node (ref "R24") (pin "2") (pinfunction "2_2") (pintype "passive"))
      (node (ref "R40") (pin "2") (pinfunction "2_2") (pintype "passive"))
    )
    (net (code "67") (name "Net-(JP109-Pad1)") (class "Default")
      (node (ref "JP109") (pin "1") (pinfunction "1_1") (pintype "passive"))
      (node (ref "JP110") (pin "1") (pinfunction "1_1") (pintype "passive"))
      (node (ref "R25") (pin "2") (pinfunction "2_2") (pintype "passive"))
      (node (ref "R41") (pin "2") (pinfunction "2_2") (pintype "passive"))
    )
    (net (code "68") (name "Net-(JP111-Pad1)") (class "Default")
      (node (ref "JP111") (pin "1") (pinfunction "1_1") (pintype "passive"))
      (node (ref "JP112") (pin "1") (pinfunction "1_1") (pintype "passive"))
      (node (ref "R26") (pin "2") (pinfunction "2_2") (pintype "passive"))
      (node (ref "R42") (pin "2") (pinfunction "2_2") (pintype "passive"))
    )
    (net (code "69") (name "Net-(JP113-Pad1)") (class "Default")
      (node (ref "JP113") (pin "1") (pinfunction "1_1") (pintype "passive"))
      (node (ref "JP114") (pin "1") (pinfunction "1_1") (pintype "passive"))
      (node (ref "R11") (pin "2") (pinfunction "2_2") (pintype "passive"))
      (node (ref "R27") (pin "2") (pinfunction "2_2") (pintype "passive"))
    )
    (net (code "70") (name "Net-(JP115-Pad1)") (class "Default")
      (node (ref "JP115") (pin "1") (pinfunction "1_1") (pintype "passive"))
      (node (ref "JP116") (pin "1") (pinfunction "1_1") (pintype "passive"))
      (node (ref "R12") (pin "2") (pinfunction "2_2") (pintype "passive"))
      (node (ref "R28") (pin "2") (pinfunction "2_2") (pintype "passive"))
    )
    (net (code "71") (name "Net-(JP117-Pad1)") (class "Default")
      (node (ref "JP117") (pin "1") (pinfunction "1_1") (pintype "passive"))
      (node (ref "JP118") (pin "1") (pinfunction "1_1") (pintype "passive"))
      (node (ref "R13") (pin "2") (pinfunction "2_2") (pintype "passive"))
      (node (ref "R29") (pin "2") (pinfunction "2_2") (pintype "passive"))
    )
    (net (code "72") (name "Net-(JP119-Pad1)") (class "Default")
      (node (ref "JP119") (pin "1") (pinfunction "1_1") (pintype "passive"))
      (node (ref "JP120") (pin "1") (pinfunction "1_1") (pintype "passive"))
      (node (ref "R14") (pin "2") (pinfunction "2_2") (pintype "passive"))
      (node (ref "R30") (pin "2") (pinfunction "2_2") (pintype "passive"))
    )
    (net (code "73") (name "Net-(JP121-Pad1)") (class "Default")
      (node (ref "JP121") (pin "1") (pinfunction "1_1") (pintype "passive"))
      (node (ref "JP122") (pin "1") (pinfunction "1_1") (pintype "passive"))
      (node (ref "R15") (pin "2") (pinfunction "2_2") (pintype "passive"))
      (node (ref "R31") (pin "2") (pinfunction "2_2") (pintype "passive"))
    )
    (net (code "74") (name "Net-(JP123-Pad1)") (class "Default")
      (node (ref "JP123") (pin "1") (pinfunction "1_1") (pintype "passive"))
      (node (ref "JP124") (pin "1") (pinfunction "1_1") (pintype "passive"))
      (node (ref "R16") (pin "2") (pinfunction "2_2") (pintype "passive"))
      (node (ref "R32") (pin "2") (pinfunction "2_2") (pintype "passive"))
    )
    (net (code "75") (name "Net-(JP125-Pad1)") (class "Default")
      (node (ref "JP125") (pin "1") (pinfunction "1_1") (pintype "passive"))
      (node (ref "JP126") (pin "1") (pinfunction "1_1") (pintype "passive"))
      (node (ref "R17") (pin "2") (pinfunction "2_2") (pintype "passive"))
      (node (ref "R33") (pin "2") (pinfunction "2_2") (pintype "passive"))
    )
    (net (code "76") (name "Net-(JP127-Pad1)") (class "Default")
      (node (ref "JP127") (pin "1") (pinfunction "1_1") (pintype "passive"))
      (node (ref "JP128") (pin "1") (pinfunction "1_1") (pintype "passive"))
      (node (ref "R18") (pin "2") (pinfunction "2_2") (pintype "passive"))
      (node (ref "R34") (pin "2") (pinfunction "2_2") (pintype "passive"))
    )
    (net (code "77") (name "Net-(LED1-PadA)") (class "Default")
      (node (ref "LED1") (pin "A") (pinfunction "A_A") (pintype "passive"))
      (node (ref "R4") (pin "2") (pinfunction "2_2") (pintype "passive"))
    )
    (net (code "78") (name "Net-(LED2-PadA)") (class "Default")
      (node (ref "LED2") (pin "A") (pinfunction "A_A") (pintype "passive"))
      (node (ref "R8") (pin "2") (pinfunction "2_2") (pintype "passive"))
    )
    (net (code "79") (name "Net-(LED3-PadA)") (class "Default")
      (node (ref "LED3") (pin "A") (pinfunction "A_A") (pintype "passive"))
      (node (ref "R9") (pin "2") (pinfunction "2_2") (pintype "passive"))
    )
    (net (code "80") (name "Net-(LED4-PadA)") (class "Default")
      (node (ref "LED4") (pin "A") (pinfunction "A_A") (pintype "passive"))
      (node (ref "R10") (pin "2") (pinfunction "2_2") (pintype "passive"))
    )
    (net (code "81") (name "Net-(LED5-PadA)") (class "Default")
      (node (ref "LED5") (pin "A") (pinfunction "A_A") (pintype "passive"))
      (node (ref "R59") (pin "2") (pinfunction "2_2") (pintype "passive"))
    )
    (net (code "82") (name "Net-(Q1-C)") (class "Default")
      (node (ref "Q1") (pin "3") (pinfunction "C_3") (pintype "passive"))
      (node (ref "R60") (pin "2") (pinfunction "2_2") (pintype "passive"))
    )
    (net (code "83") (name "Net-(Q2-B)") (class "Default")
      (node (ref "Q2") (pin "1") (pinfunction "B_1") (pintype "passive"))
      (node (ref "R60") (pin "1") (pinfunction "1_1") (pintype "passive"))
    )
    (net (code "84") (name "Net-(Q3-C)") (class "Default")
      (node (ref "Q3") (pin "3") (pinfunction "C_3") (pintype "passive"))
      (node (ref "R61") (pin "2") (pinfunction "2_2") (pintype "passive"))
    )
    (net (code "85") (name "Net-(Q4-B)") (class "Default")
      (node (ref "Q4") (pin "1") (pinfunction "B_1") (pintype "passive"))
      (node (ref "R61") (pin "1") (pinfunction "1_1") (pintype "passive"))
    )
    (net (code "86") (name "Net-(TR1-B)") (class "Default")
      (node (ref "R11") (pin "1") (pinfunction "1_1") (pintype "passive"))
      (node (ref "TR1") (pin "4") (pinfunction "B_4") (pintype "bidirectional"))
    )
    (net (code "87") (name "Net-(TR2-B)") (class "Default")
      (node (ref "R12") (pin "1") (pinfunction "1_1") (pintype "passive"))
      (node (ref "TR2") (pin "4") (pinfunction "B_4") (pintype "bidirectional"))
    )
    (net (code "88") (name "Net-(TR3-B)") (class "Default")
      (node (ref "R13") (pin "1") (pinfunction "1_1") (pintype "passive"))
      (node (ref "TR3") (pin "4") (pinfunction "B_4") (pintype "bidirectional"))
    )
    (net (code "89") (name "Net-(TR4-B)") (class "Default")
      (node (ref "R14") (pin "1") (pinfunction "1_1") (pintype "passive"))
      (node (ref "TR4") (pin "4") (pinfunction "B_4") (pintype "bidirectional"))
    )
    (net (code "90") (name "Net-(TR5-B)") (class "Default")
      (node (ref "R15") (pin "1") (pinfunction "1_1") (pintype "passive"))
      (node (ref "TR5") (pin "4") (pinfunction "B_4") (pintype "bidirectional"))
    )
    (net (code "91") (name "Net-(TR6-B)") (class "Default")
      (node (ref "R16") (pin "1") (pinfunction "1_1") (pintype "passive"))
      (node (ref "TR6") (pin "4") (pinfunction "B_4") (pintype "bidirectional"))
    )
    (net (code "92") (name "Net-(TR7-B)") (class "Default")
      (node (ref "R17") (pin "1") (pinfunction "1_1") (pintype "passive"))
      (node (ref "TR7") (pin "4") (pinfunction "B_4") (pintype "bidirectional"))
    )
    (net (code "93") (name "Net-(TR8-B)") (class "Default")
      (node (ref "R18") (pin "1") (pinfunction "1_1") (pintype "passive"))
      (node (ref "TR8") (pin "4") (pinfunction "B_4") (pintype "bidirectional"))
    )
    (net (code "94") (name "Net-(TR9-B)") (class "Default")
      (node (ref "R19") (pin "1") (pinfunction "1_1") (pintype "passive"))
      (node (ref "TR9") (pin "4") (pinfunction "B_4") (pintype "bidirectional"))
    )
    (net (code "95") (name "Net-(TR10-B)") (class "Default")
      (node (ref "R20") (pin "1") (pinfunction "1_1") (pintype "passive"))
      (node (ref "TR10") (pin "4") (pinfunction "B_4") (pintype "bidirectional"))
    )
    (net (code "96") (name "Net-(TR11-B)") (class "Default")
      (node (ref "R21") (pin "1") (pinfunction "1_1") (pintype "passive"))
      (node (ref "TR11") (pin "4") (pinfunction "B_4") (pintype "bidirectional"))
    )
    (net (code "97") (name "Net-(TR12-B)") (class "Default")
      (node (ref "R22") (pin "1") (pinfunction "1_1") (pintype "passive"))
      (node (ref "TR12") (pin "4") (pinfunction "B_4") (pintype "bidirectional"))
    )
    (net (code "98") (name "Net-(TR13-B)") (class "Default")
      (node (ref "R23") (pin "1") (pinfunction "1_1") (pintype "passive"))
      (node (ref "TR13") (pin "4") (pinfunction "B_4") (pintype "bidirectional"))
    )
    (net (code "99") (name "Net-(TR14-B)") (class "Default")
      (node (ref "R24") (pin "1") (pinfunction "1_1") (pintype "passive"))
      (node (ref "TR14") (pin "4") (pinfunction "B_4") (pintype "bidirectional"))
    )
    (net (code "100") (name "Net-(TR15-B)") (class "Default")
      (node (ref "R25") (pin "1") (pinfunction "1_1") (pintype "passive"))
      (node (ref "TR15") (pin "4") (pinfunction "B_4") (pintype "bidirectional"))
    )
    (net (code "101") (name "Net-(TR16-B)") (class "Default")
      (node (ref "R26") (pin "1") (pinfunction "1_1") (pintype "passive"))
      (node (ref "TR16") (pin "4") (pinfunction "B_4") (pintype "bidirectional"))
    )
    (net (code "102") (name "Net-(U$1-RA2)") (class "Default")
      (node (ref "C39") (pin "1") (pinfunction "1_1") (pintype "passive"))
      (node (ref "R62") (pin "2") (pinfunction "2_2") (pintype "passive"))
      (node (ref "R63") (pin "2") (pinfunction "2_2") (pintype "passive"))
      (node (ref "U$1") (pin "4") (pinfunction "RA2_4") (pintype "bidirectional"))
    )
    (net (code "103") (name "RESET_N") (class "Default")
      (node (ref "IC1") (pin "37") (pinfunction "PROGRAM_B_2_37") (pintype "bidirectional"))
      (node (ref "R6") (pin "1") (pinfunction "1_1") (pintype "passive"))
      (node (ref "TP1") (pin "TP") (pinfunction "TP_TP") (pintype "input"))
    )
    (net (code "104") (name "S1") (class "Default")
      (node (ref "IC1") (pin "140") (pinfunction "IO_L3P_0_140") (pintype "bidirectional"))
      (node (ref "TR1") (pin "3") (pinfunction "A_3") (pintype "bidirectional"))
    )
    (net (code "105") (name "S2") (class "Default")
      (node (ref "IC1") (pin "142") (pinfunction "IO_L2P_0_142") (pintype "bidirectional"))
      (node (ref "TR2") (pin "3") (pinfunction "A_3") (pintype "bidirectional"))
    )
    (net (code "106") (name "S3") (class "Default")
      (node (ref "IC1") (pin "2") (pinfunction "IO_L83P_3_2") (pintype "bidirectional"))
      (node (ref "TR3") (pin "3") (pinfunction "A_3") (pintype "bidirectional"))
    )
    (net (code "107") (name "S4") (class "Default")
      (node (ref "IC1") (pin "6") (pinfunction "IO_L52P_3_6") (pintype "bidirectional"))
      (node (ref "TR4") (pin "3") (pinfunction "A_3") (pintype "bidirectional"))
    )
    (net (code "108") (name "S5") (class "Default")
      (node (ref "IC1") (pin "8") (pinfunction "IO_L51P_3_8") (pintype "bidirectional"))
      (node (ref "TR5") (pin "3") (pinfunction "A_3") (pintype "bidirectional"))
    )
    (net (code "109") (name "S6") (class "Default")
      (node (ref "IC1") (pin "10") (pinfunction "IO_L50P_3_10") (pintype "bidirectional"))
      (node (ref "TR6") (pin "3") (pinfunction "A_3") (pintype "bidirectional"))
    )
    (net (code "110") (name "S7") (class "Default")
      (node (ref "IC1") (pin "12") (pinfunction "IO_L49P_3_12") (pintype "bidirectional"))
      (node (ref "TR7") (pin "3") (pinfunction "A_3") (pintype "bidirectional"))
    )
    (net (code "111") (name "S8") (class "Default")
      (node (ref "IC1") (pin "15") (pinfunction "IO_L44P_GCLK21_3_15") (pintype "bidirectional"))
      (node (ref "TR8") (pin "3") (pinfunction "A_3") (pintype "bidirectional"))
    )
    (net (code "112") (name "S9") (class "Default")
      (node (ref "IC1") (pin "21") (pinfunction "IO_L42N_GCLK24_3_21") (pintype "bidirectional"))
      (node (ref "TR9") (pin "3") (pinfunction "A_3") (pintype "bidirectional"))
    )
    (net (code "113") (name "S10") (class "Default")
      (node (ref "IC1") (pin "23") (pinfunction "IO_L41N_GCLK26_3_23") (pintype "bidirectional"))
      (node (ref "TR10") (pin "3") (pinfunction "A_3") (pintype "bidirectional"))
    )
    (net (code "114") (name "S11") (class "Default")
      (node (ref "IC1") (pin "26") (pinfunction "IO_L37N_3_26") (pintype "bidirectional"))
      (node (ref "TR11") (pin "3") (pinfunction "A_3") (pintype "bidirectional"))
    )
    (net (code "115") (name "S12") (class "Default")
      (node (ref "IC1") (pin "29") (pinfunction "IO_L36N_3_29") (pintype "bidirectional"))
      (node (ref "TR12") (pin "3") (pinfunction "A_3") (pintype "bidirectional"))
    )
    (net (code "116") (name "S13") (class "Default")
      (node (ref "IC1") (pin "32") (pinfunction "IO_L2N_3_32") (pintype "bidirectional"))
      (node (ref "TR13") (pin "3") (pinfunction "A_3") (pintype "bidirectional"))
    )
    (net (code "117") (name "S14") (class "Default")
      (node (ref "IC1") (pin "34") (pinfunction "IO_L1N_VREF_3_34") (pintype "bidirectional"))
      (node (ref "TR14") (pin "3") (pinfunction "A_3") (pintype "bidirectional"))
    )
    (net (code "118") (name "S15") (class "Default")
      (node (ref "IC1") (pin "39") (pinfunction "IO_L65P_INIT_B_2_39") (pintype "bidirectional"))
      (node (ref "TR15") (pin "3") (pinfunction "A_3") (pintype "bidirectional"))
    )
    (net (code "119") (name "S16") (class "Default")
      (node (ref "IC1") (pin "41") (pinfunction "IO_L64P_D8_2_41") (pintype "bidirectional"))
      (node (ref "TR16") (pin "3") (pinfunction "A_3") (pintype "bidirectional"))
    )
    (net (code "120") (name "SD1") (class "Default")
      (node (ref "IC1") (pin "141") (pinfunction "IO_L2N_0_141") (pintype "bidirectional"))
      (node (ref "R43") (pin "2") (pinfunction "2_2") (pintype "passive"))
      (node (ref "TR1") (pin "5") (pinfunction "DIR_5") (pintype "input"))
    )
    (net (code "121") (name "SD2") (class "Default")
      (node (ref "IC1") (pin "143") (pinfunction "IO_L1N_VREF_0_143") (pintype "bidirectional"))
      (node (ref "R44") (pin "2") (pinfunction "2_2") (pintype "passive"))
      (node (ref "TR2") (pin "5") (pinfunction "DIR_5") (pintype "input"))
    )
    (net (code "122") (name "SD3") (class "Default")
      (node (ref "IC1") (pin "5") (pinfunction "IO_L52N_3_5") (pintype "bidirectional"))
      (node (ref "R45") (pin "2") (pinfunction "2_2") (pintype "passive"))
      (node (ref "TR3") (pin "5") (pinfunction "DIR_5") (pintype "input"))
    )
    (net (code "123") (name "SD4") (class "Default")
      (node (ref "IC1") (pin "7") (pinfunction "IO_L51N_3_7") (pintype "bidirectional"))
      (node (ref "R46") (pin "2") (pinfunction "2_2") (pintype "passive"))
      (node (ref "TR4") (pin "5") (pinfunction "DIR_5") (pintype "input"))
    )
    (net (code "124") (name "SD5") (class "Default")
      (node (ref "IC1") (pin "9") (pinfunction "IO_L50N_3_9") (pintype "bidirectional"))
      (node (ref "R47") (pin "2") (pinfunction "2_2") (pintype "passive"))
      (node (ref "TR5") (pin "5") (pinfunction "DIR_5") (pintype "input"))
    )
    (net (code "125") (name "SD6") (class "Default")
      (node (ref "IC1") (pin "11") (pinfunction "IO_L49N_3_11") (pintype "bidirectional"))
      (node (ref "R48") (pin "2") (pinfunction "2_2") (pintype "passive"))
      (node (ref "TR6") (pin "5") (pinfunction "DIR_5") (pintype "input"))
    )
    (net (code "126") (name "SD7") (class "Default")
      (node (ref "IC1") (pin "14") (pinfunction "IO_L44N_GCLK20_3_14") (pintype "bidirectional"))
      (node (ref "R49") (pin "2") (pinfunction "2_2") (pintype "passive"))
      (node (ref "TR7") (pin "5") (pinfunction "DIR_5") (pintype "input"))
    )
    (net (code "127") (name "SD8") (class "Default")
      (node (ref "IC1") (pin "16") (pinfunction "IO_L43N_GCLK22_IRDY2_3_16") (pintype "bidirectional"))
      (node (ref "R50") (pin "2") (pinfunction "2_2") (pintype "passive"))
      (node (ref "TR8") (pin "5") (pinfunction "DIR_5") (pintype "input"))
    )
    (net (code "128") (name "SD9") (class "Default")
      (node (ref "IC1") (pin "22") (pinfunction "IO_L42P_GCLK25_TRDY2_3_22") (pintype "bidirectional"))
      (node (ref "R51") (pin "2") (pinfunction "2_2") (pintype "passive"))
      (node (ref "TR9") (pin "5") (pinfunction "DIR_5") (pintype "input"))
    )
    (net (code "129") (name "SD10") (class "Default")
      (node (ref "IC1") (pin "24") (pinfunction "IO_L41P_GCLK27_3_24") (pintype "bidirectional"))
      (node (ref "R52") (pin "2") (pinfunction "2_2") (pintype "passive"))
      (node (ref "TR10") (pin "5") (pinfunction "DIR_5") (pintype "input"))
    )
    (net (code "130") (name "SD11") (class "Default")
      (node (ref "IC1") (pin "27") (pinfunction "IO_L37P_3_27") (pintype "bidirectional"))
      (node (ref "R53") (pin "2") (pinfunction "2_2") (pintype "passive"))
      (node (ref "TR11") (pin "5") (pinfunction "DIR_5") (pintype "input"))
    )
    (net (code "131") (name "SD12") (class "Default")
      (node (ref "IC1") (pin "30") (pinfunction "IO_L36P_3_30") (pintype "bidirectional"))
      (node (ref "R54") (pin "2") (pinfunction "2_2") (pintype "passive"))
      (node (ref "TR12") (pin "5") (pinfunction "DIR_5") (pintype "input"))
    )
    (net (code "132") (name "SD13") (class "Default")
      (node (ref "IC1") (pin "33") (pinfunction "IO_L2P_3_33") (pintype "bidirectional"))
      (node (ref "R55") (pin "2") (pinfunction "2_2") (pintype "passive"))
      (node (ref "TR13") (pin "5") (pinfunction "DIR_5") (pintype "input"))
    )
    (net (code "133") (name "SD14") (class "Default")
      (node (ref "IC1") (pin "35") (pinfunction "IO_L1P_3_35") (pintype "bidirectional"))
      (node (ref "R56") (pin "2") (pinfunction "2_2") (pintype "passive"))
      (node (ref "TR14") (pin "5") (pinfunction "DIR_5") (pintype "input"))
    )
    (net (code "134") (name "SD15") (class "Default")
      (node (ref "IC1") (pin "40") (pinfunction "IO_L64N_D9_2_40") (pintype "bidirectional"))
      (node (ref "R57") (pin "2") (pinfunction "2_2") (pintype "passive"))
      (node (ref "TR15") (pin "5") (pinfunction "DIR_5") (pintype "input"))
    )
    (net (code "135") (name "SD16") (class "Default")
      (node (ref "IC1") (pin "43") (pinfunction "IO_L62N_D6_2_43") (pintype "bidirectional"))
      (node (ref "R58") (pin "2") (pinfunction "2_2") (pintype "passive"))
      (node (ref "TR16") (pin "5") (pinfunction "DIR_5") (pintype "input"))
    )
    (net (code "136") (name "TCK") (class "Default")
      (node (ref "IC1") (pin "109") (pinfunction "TCK_109") (pintype "input"))
      (node (ref "TP14") (pin "TP") (pinfunction "TP_TP") (pintype "input"))
    )
    (net (code "137") (name "TDI") (class "Default")
      (node (ref "IC1") (pin "110") (pinfunction "TDI_110") (pintype "input"))
      (node (ref "TP15") (pin "TP") (pinfunction "TP_TP") (pintype "input"))
    )
    (net (code "138") (name "TDO") (class "Default")
      (node (ref "IC1") (pin "106") (pinfunction "TDO_106") (pintype "output"))
      (node (ref "TP16") (pin "TP") (pinfunction "TP_TP") (pintype "input"))
    )
    (net (code "139") (name "TMS") (class "Default")
      (node (ref "IC1") (pin "107") (pinfunction "TMS_107") (pintype "input"))
      (node (ref "TP13") (pin "TP") (pinfunction "TP_TP") (pintype "input"))
    )
    (net (code "140") (name "USB_D+") (class "Default")
      (node (ref "IC1") (pin "59") (pinfunction "IO_L13N_D10_2_59") (pintype "bidirectional"))
      (node (ref "R2") (pin "2") (pinfunction "2_2") (pintype "passive"))
    )
    (net (code "141") (name "USB_D-") (class "Default")
      (node (ref "IC1") (pin "56") (pinfunction "IO_L30P_GCLK1_D13_2_56") (pintype "bidirectional"))
      (node (ref "R1") (pin "2") (pinfunction "2_2") (pintype "passive"))
    )
    (net (code "142") (name "USB_PUP") (class "Default")
      (node (ref "IC1") (pin "67") (pinfunction "IO_L2P_CMPCLK_2_67") (pintype "bidirectional"))
      (node (ref "R3") (pin "2") (pinfunction "2_2") (pintype "passive"))
    )
    (net (code "143") (name "USB_S+") (class "Default")
      (node (ref "IC1") (pin "58") (pinfunction "IO_L14P_D11_2_58") (pintype "bidirectional"))
      (node (ref "R2") (pin "1") (pinfunction "1_1") (pintype "passive"))
      (node (ref "R3") (pin "1") (pinfunction "1_1") (pintype "passive"))
      (node (ref "X1") (pin "3") (pinfunction "D+_3") (pintype "bidirectional"))
    )
    (net (code "144") (name "USB_S-") (class "Default")
      (node (ref "IC1") (pin "57") (pinfunction "IO_L14N_D12_2_57") (pintype "bidirectional"))
      (node (ref "R1") (pin "1") (pinfunction "1_1") (pintype "passive"))
      (node (ref "X1") (pin "2") (pinfunction "D-_2") (pintype "bidirectional"))
    )
    (net (code "145") (name "VCCINT") (class "Default")
      (node (ref "C18") (pin "1") (pinfunction "1_1") (pintype "passive"))
      (node (ref "C19") (pin "1") (pinfunction "1_1") (pintype "passive"))
      (node (ref "C20") (pin "1") (pinfunction "1_1") (pintype "passive"))
      (node (ref "IC1") (pin "128") (pinfunction "VCCINT_128") (pintype "power_in"))
      (node (ref "IC1") (pin "19") (pinfunction "VCCINT_19") (pintype "power_in"))
      (node (ref "IC1") (pin "28") (pinfunction "VCCINT_28") (pintype "power_in"))
      (node (ref "IC1") (pin "52") (pinfunction "VCCINT_52") (pintype "power_in"))
      (node (ref "IC1") (pin "89") (pinfunction "VCCINT_89") (pintype "power_in"))
      (node (ref "L1") (pin "2") (pinfunction "2_2") (pintype "passive"))
    )
    (net (code "146") (name "VCCIO") (class "Default")
      (node (ref "C10") (pin "1") (pinfunction "1_1") (pintype "passive"))
      (node (ref "C11") (pin "1") (pinfunction "1_1") (pintype "passive"))
      (node (ref "C12") (pin "1") (pinfunction "1_1") (pintype "passive"))
      (node (ref "C3") (pin "1") (pinfunction "1_1") (pintype "passive"))
      (node (ref "C4") (pin "1") (pinfunction "1_1") (pintype "passive"))
      (node (ref "C7") (pin "1") (pinfunction "1_1") (pintype "passive"))
      (node (ref "C8") (pin "1") (pinfunction "1_1") (pintype "passive"))
      (node (ref "C9") (pin "1") (pinfunction "1_1") (pintype "passive"))
      (node (ref "IC1") (pin "129") (pinfunction "VCCAUX_129") (pintype "power_in"))
      (node (ref "IC1") (pin "20") (pinfunction "VCCAUX_20") (pintype "power_in"))
      (node (ref "IC1") (pin "36") (pinfunction "VCCAUX_36") (pintype "power_in"))
      (node (ref "IC1") (pin "53") (pinfunction "VCCAUX_53") (pintype "power_in"))
      (node (ref "IC1") (pin "90") (pinfunction "VCCAUX_90") (pintype "power_in"))
      (node (ref "L2") (pin "2") (pinfunction "2_2") (pintype "passive"))
    )
    (net (code "147") (name "VCC_B1") (class "Default")
      (node (ref "C34") (pin "1") (pinfunction "1_1") (pintype "passive"))
      (node (ref "JP3") (pin "1") (pinfunction "1_1") (pintype "passive"))
      (node (ref "JP4") (pin "1") (pinfunction "1_1") (pintype "passive"))
      (node (ref "TR1") (pin "6") (pinfunction "VCCB_6") (pintype "passive"))
      (node (ref "TR2") (pin "6") (pinfunction "VCCB_6") (pintype "passive"))
      (node (ref "TR3") (pin "6") (pinfunction "VCCB_6") (pintype "passive"))
      (node (ref "TR4") (pin "6") (pinfunction "VCCB_6") (pintype "passive"))
      (node (ref "TR5") (pin "6") (pinfunction "VCCB_6") (pintype "passive"))
      (node (ref "TR6") (pin "6") (pinfunction "VCCB_6") (pintype "passive"))
      (node (ref "TR7") (pin "6") (pinfunction "VCCB_6") (pintype "passive"))
      (node (ref "TR8") (pin "6") (pinfunction "VCCB_6") (pintype "passive"))
    )
    (net (code "148") (name "VCC_B2") (class "Default")
      (node (ref "C35") (pin "1") (pinfunction "1_1") (pintype "passive"))
      (node (ref "JP1") (pin "1") (pinfunction "1_1") (pintype "passive"))
      (node (ref "JP2") (pin "1") (pinfunction "1_1") (pintype "passive"))
      (node (ref "Q2") (pin "3") (pinfunction "C_3") (pintype "passive"))
      (node (ref "Q4") (pin "3") (pinfunction "C_3") (pintype "passive"))
      (node (ref "R63") (pin "1") (pinfunction "1_1") (pintype "passive"))
      (node (ref "TR10") (pin "6") (pinfunction "VCCB_6") (pintype "passive"))
      (node (ref "TR11") (pin "6") (pinfunction "VCCB_6") (pintype "passive"))
      (node (ref "TR12") (pin "6") (pinfunction "VCCB_6") (pintype "passive"))
      (node (ref "TR13") (pin "6") (pinfunction "VCCB_6") (pintype "passive"))
      (node (ref "TR14") (pin "6") (pinfunction "VCCB_6") (pintype "passive"))
      (node (ref "TR15") (pin "6") (pinfunction "VCCB_6") (pintype "passive"))
      (node (ref "TR16") (pin "6") (pinfunction "VCCB_6") (pintype "passive"))
      (node (ref "TR9") (pin "6") (pinfunction "VCCB_6") (pintype "passive"))
    )
    (net (code "149") (name "VIO33") (class "Default")
      (node (ref "IC1") (pin "44") (pinfunction "IO_L62P_D5_2_44") (pintype "bidirectional"))
      (node (ref "Q3") (pin "1") (pinfunction "B_1") (pintype "passive"))
    )
    (net (code "150") (name "VIO50") (class "Default")
      (node (ref "IC1") (pin "45") (pinfunction "IO_L49N_D4_2_45") (pintype "bidirectional"))
      (node (ref "Q1") (pin "1") (pinfunction "B_1") (pintype "passive"))
    )
    (net (code "151") (name "unconnected-(IC1-CMPCS_B_2-Pad72)") (class "Default")
      (node (ref "IC1") (pin "72") (pinfunction "CMPCS_B_2_72") (pintype "bidirectional"))
    )
    (net (code "152") (name "unconnected-(IC1-IO_L2N_CMPMOSI_2-Pad66)") (class "Default")
      (node (ref "IC1") (pin "66") (pinfunction "IO_L2N_CMPMOSI_2_66") (pintype "bidirectional"))
    )
    (net (code "153") (name "unconnected-(IC1-IO_L4N_0-Pad137)") (class "Default")
      (node (ref "IC1") (pin "137") (pinfunction "IO_L4N_0_137") (pintype "bidirectional"))
    )
    (net (code "154") (name "unconnected-(IC1-IO_L12N_D2_MISO3_2-Pad61)") (class "Default")
      (node (ref "IC1") (pin "61") (pinfunction "IO_L12N_D2_MISO3_2_61") (pintype "bidirectional"))
    )
    (net (code "155") (name "unconnected-(IC1-IO_L12P_D1_MISO2_2-Pad62)") (class "Default")
      (node (ref "IC1") (pin "62") (pinfunction "IO_L12P_D1_MISO2_2_62") (pintype "bidirectional"))
    )
    (net (code "156") (name "unconnected-(IC1-IO_L30N_GCLK0_USERCCLK_2-Pad55)") (class "Default")
      (node (ref "IC1") (pin "55") (pinfunction "IO_L30N_GCLK0_USERCCLK_2_55") (pintype "bidirectional"))
    )
    (net (code "157") (name "unconnected-(IC1-IO_L31N_GCLK30_D15_2-Pad50)") (class "Default")
      (node (ref "IC1") (pin "50") (pinfunction "IO_L31N_GCLK30_D15_2_50") (pintype "bidirectional"))
    )
    (net (code "158") (name "unconnected-(IC1-IO_L43P_GCLK23_3-Pad17)") (class "Default")
      (node (ref "IC1") (pin "17") (pinfunction "IO_L43P_GCLK23_3_17") (pintype "bidirectional"))
    )
    (net (code "159") (name "unconnected-(IC1-IO_L48P_D7_2-Pad48)") (class "Default")
      (node (ref "IC1") (pin "48") (pinfunction "IO_L48P_D7_2_48") (pintype "bidirectional"))
    )
    (net (code "160") (name "unconnected-(IC1-IO_L83N_VREF_3-Pad1)") (class "Default")
      (node (ref "IC1") (pin "1") (pinfunction "IO_L83N_VREF_3_1") (pintype "bidirectional"))
    )
    (net (code "161") (name "unconnected-(IC3-NC-Pad4)") (class "Default")
      (node (ref "IC3") (pin "4") (pinfunction "NC_4") (pintype "no_connect"))
    )
    (net (code "162") (name "unconnected-(IC4A-NC-Pad40)") (class "Default")
      (node (ref "IC4") (pin "40") (pinfunction "NC_40") (pintype "no_connect"))
    )
  )
)
